# LiPoLoader.net
KiCad netlist of a schematic drawn in EAGLE
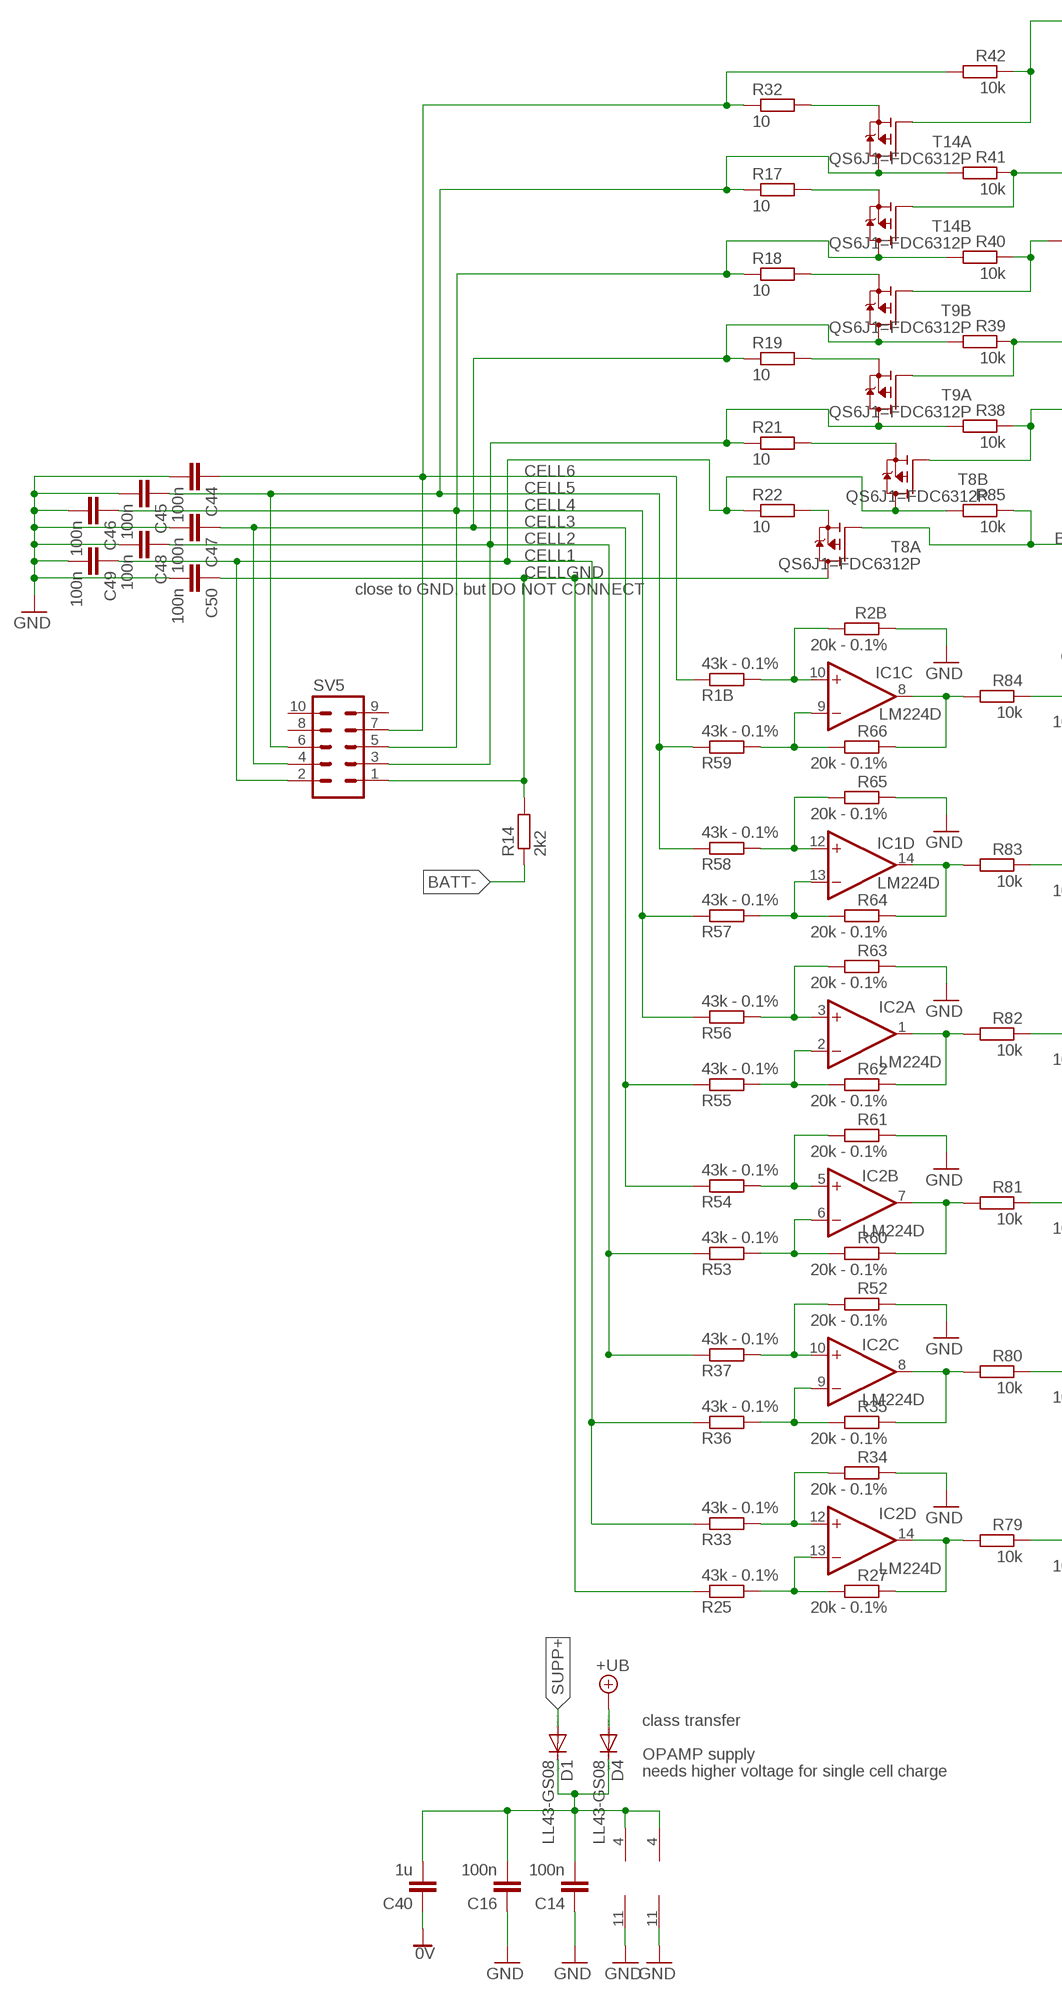
[diagram p0: schematic, sheet 1, part 1 of 2]
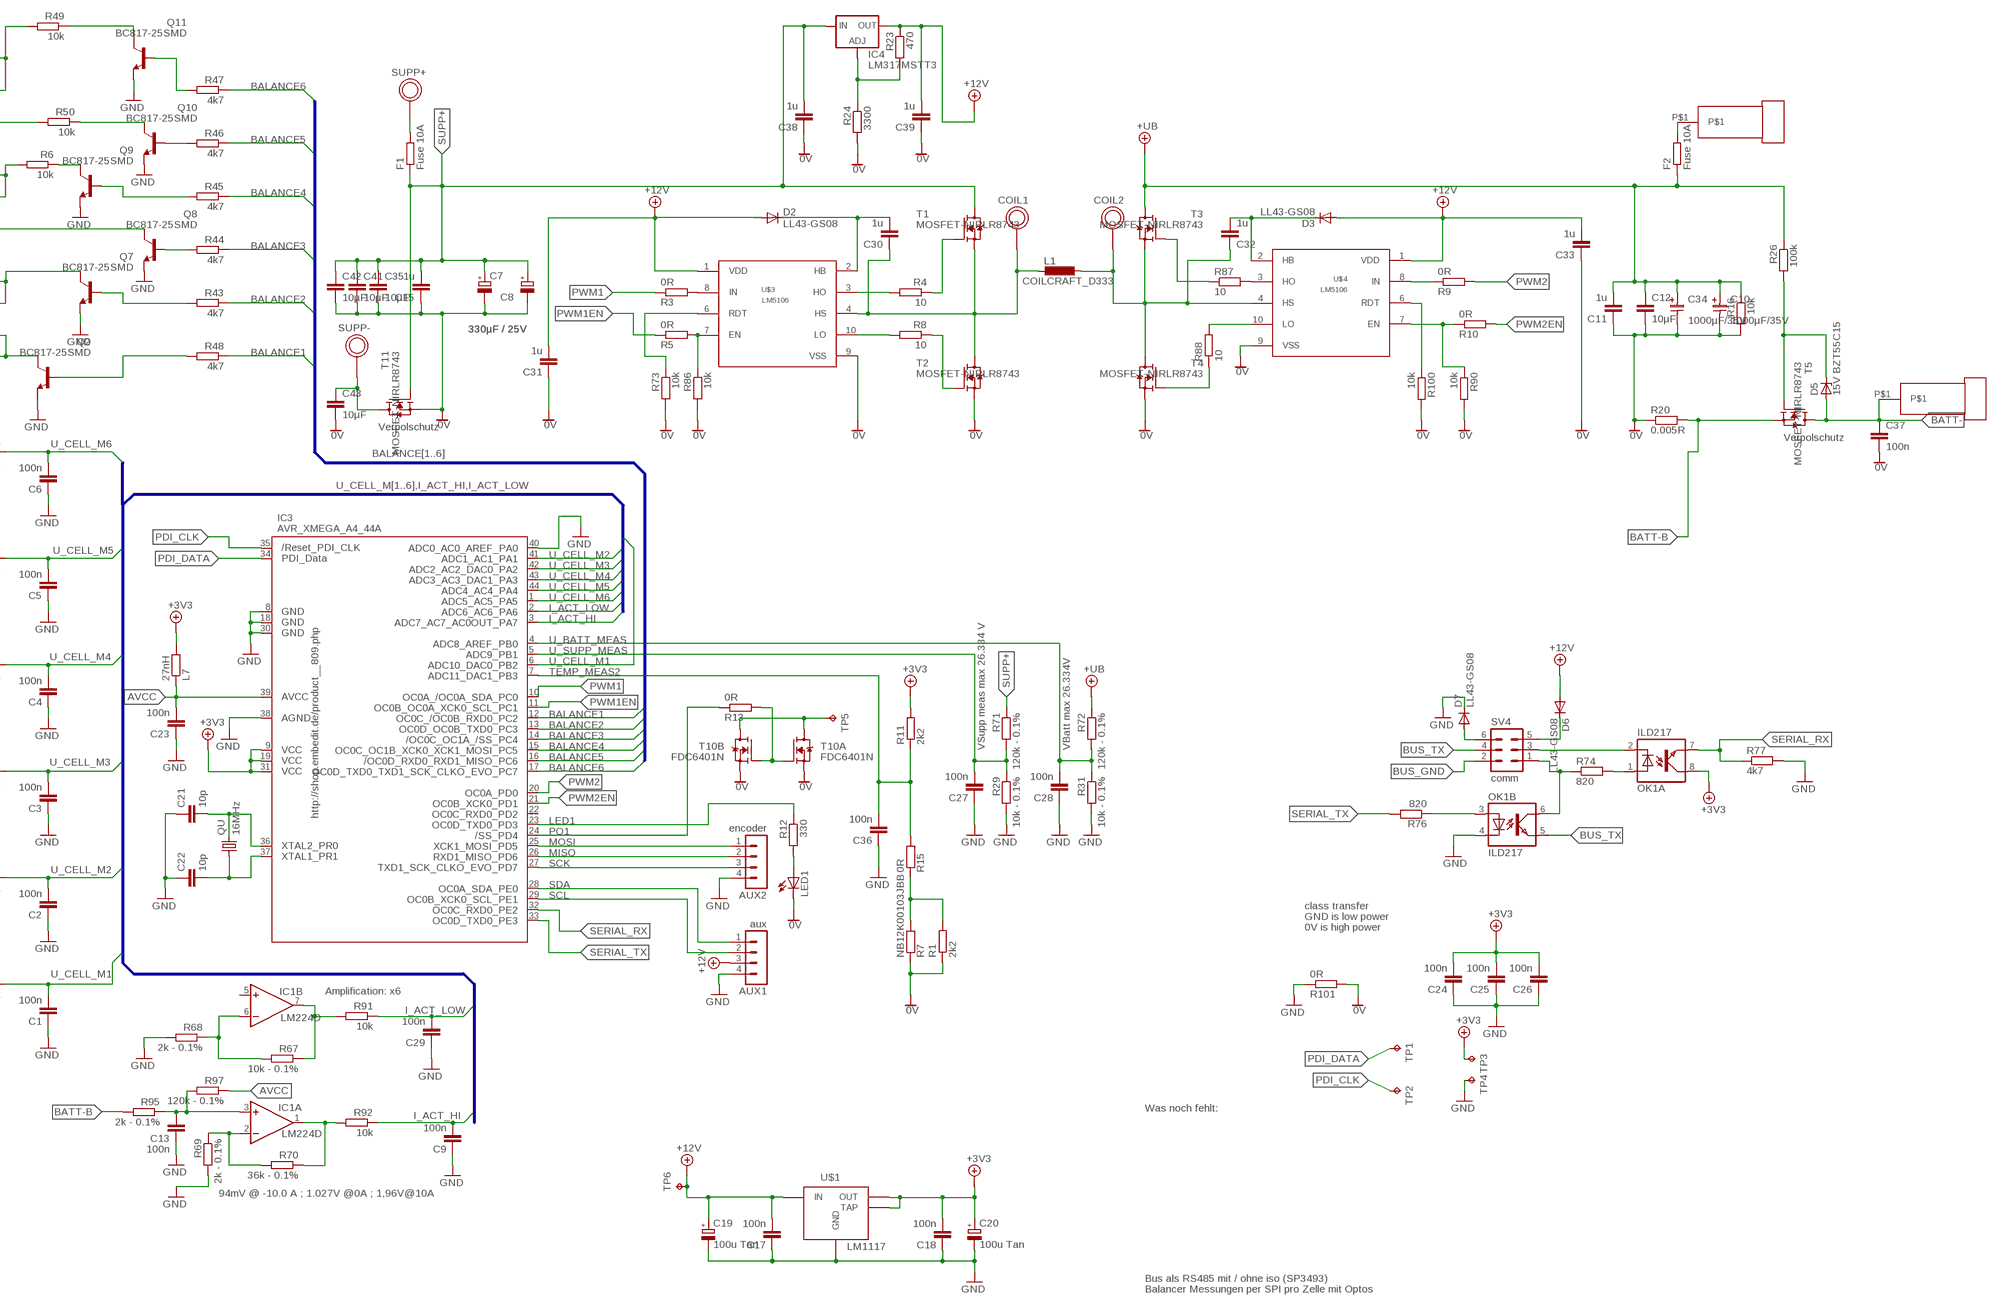
[diagram p1: schematic, sheet 1, part 2 of 2]

(export (version "E")
  (design (tool "Eeschema 10.0.6"))
  (components
    (comp (ref "AUX1")
      (value "aux")
      (footprint "eagle-import:MA04-1")
      (libsource (lib "eagle-import") (part "MA04-1"))
    )
    (comp (ref "AUX2")
      (value "encoder")
      (footprint "eagle-import:MA04-1")
      (libsource (lib "eagle-import") (part "MA04-1"))
    )
    (comp (ref "C1")
      (value "100n")
      (footprint "eagle-import:C0603K")
      (libsource (lib "eagle-import") (part "C-EUC0603K"))
    )
    (comp (ref "C2")
      (value "100n")
      (footprint "eagle-import:C0603K")
      (libsource (lib "eagle-import") (part "C-EUC0603K"))
    )
    (comp (ref "C3")
      (value "100n")
      (footprint "eagle-import:C0603K")
      (libsource (lib "eagle-import") (part "C-EUC0603K"))
    )
    (comp (ref "C4")
      (value "100n")
      (footprint "eagle-import:C0603K")
      (libsource (lib "eagle-import") (part "C-EUC0603K"))
    )
    (comp (ref "C5")
      (value "100n")
      (footprint "eagle-import:C0603K")
      (libsource (lib "eagle-import") (part "C-EUC0603K"))
    )
    (comp (ref "C6")
      (value "100n")
      (footprint "eagle-import:C0603K")
      (libsource (lib "eagle-import") (part "C-EUC0603K"))
    )
    (comp (ref "C7")
      (value "330µF / 25V")
      (footprint "eagle-import:E3,5-8")
      (libsource (lib "eagle-import") (part "CPOL-EUE3.5-8"))
    )
    (comp (ref "C8")
      (value "330µF / 25V")
      (footprint "eagle-import:E3,5-8")
      (libsource (lib "eagle-import") (part "CPOL-EUE3.5-8"))
    )
    (comp (ref "C9")
      (value "100n")
      (footprint "eagle-import:C0603K")
      (libsource (lib "eagle-import") (part "C-EUC0603K"))
    )
    (comp (ref "C10")
      (value "1000µF/35V")
      (footprint "eagle-import:E5-13-L")
      (libsource (lib "eagle-import") (part "CPOL"))
    )
    (comp (ref "C11")
      (value "1u")
      (footprint "eagle-import:C1206K")
      (libsource (lib "eagle-import") (part "C-EUC1206K"))
    )
    (comp (ref "C12")
      (value "10µF")
      (footprint "eagle-import:C1206K")
      (libsource (lib "eagle-import") (part "C-EUC1206K"))
    )
    (comp (ref "C13")
      (value "100n")
      (footprint "eagle-import:C0603K")
      (libsource (lib "eagle-import") (part "C-EUC0603K"))
    )
    (comp (ref "C14")
      (value "100n")
      (footprint "eagle-import:C0603K")
      (libsource (lib "eagle-import") (part "C-EUC0603K"))
    )
    (comp (ref "C15")
      (value "1u")
      (footprint "eagle-import:C1206K")
      (libsource (lib "eagle-import") (part "C-EUC1206K"))
    )
    (comp (ref "C16")
      (value "100n")
      (footprint "eagle-import:C0603K")
      (libsource (lib "eagle-import") (part "C-EUC0603K"))
    )
    (comp (ref "C17")
      (value "100n")
      (footprint "eagle-import:C0603K")
      (libsource (lib "eagle-import") (part "C-EUC0603K"))
    )
    (comp (ref "C18")
      (value "100n")
      (footprint "eagle-import:C0603K")
      (libsource (lib "eagle-import") (part "C-EUC0603K"))
    )
    (comp (ref "C19")
      (value "100u Tan")
      (footprint "eagle-import:SMC_C")
      (libsource (lib "eagle-import") (part "CPOL-EUSMCC"))
    )
    (comp (ref "C20")
      (value "100u Tan")
      (footprint "eagle-import:SMC_C")
      (libsource (lib "eagle-import") (part "CPOL-EUSMCC"))
    )
    (comp (ref "C21")
      (value "10p")
      (footprint "eagle-import:C0603")
      (libsource (lib "eagle-import") (part "C-EUC0603"))
    )
    (comp (ref "C22")
      (value "10p")
      (footprint "eagle-import:C0603")
      (libsource (lib "eagle-import") (part "C-EUC0603"))
    )
    (comp (ref "C23")
      (value "100n")
      (footprint "eagle-import:C0603K")
      (libsource (lib "eagle-import") (part "C-EUC0603K"))
    )
    (comp (ref "C24")
      (value "100n")
      (footprint "eagle-import:C0603K")
      (libsource (lib "eagle-import") (part "C-EUC0603K"))
    )
    (comp (ref "C25")
      (value "100n")
      (footprint "eagle-import:C0603K")
      (libsource (lib "eagle-import") (part "C-EUC0603K"))
    )
    (comp (ref "C26")
      (value "100n")
      (footprint "eagle-import:C0603K")
      (libsource (lib "eagle-import") (part "C-EUC0603K"))
    )
    (comp (ref "C27")
      (value "100n")
      (footprint "eagle-import:C0603K")
      (libsource (lib "eagle-import") (part "C-EUC0603K"))
    )
    (comp (ref "C28")
      (value "100n")
      (footprint "eagle-import:C0603K")
      (libsource (lib "eagle-import") (part "C-EUC0603K"))
    )
    (comp (ref "C29")
      (value "100n")
      (footprint "eagle-import:C0603K")
      (libsource (lib "eagle-import") (part "C-EUC0603K"))
    )
    (comp (ref "C30")
      (value "1u")
      (footprint "eagle-import:C1206K")
      (libsource (lib "eagle-import") (part "C-EUC1206K"))
    )
    (comp (ref "C31")
      (value "1u")
      (footprint "eagle-import:C1206K")
      (libsource (lib "eagle-import") (part "C-EUC1206K"))
    )
    (comp (ref "C32")
      (value "1u")
      (footprint "eagle-import:C1206K")
      (libsource (lib "eagle-import") (part "C-EUC1206K"))
    )
    (comp (ref "C33")
      (value "1u")
      (footprint "eagle-import:C1206K")
      (libsource (lib "eagle-import") (part "C-EUC1206K"))
    )
    (comp (ref "C34")
      (value "1000µF/35V")
      (footprint "eagle-import:E5-13-L")
      (libsource (lib "eagle-import") (part "CPOL"))
    )
    (comp (ref "C35")
      (value "10µF")
      (footprint "eagle-import:C1206K")
      (libsource (lib "eagle-import") (part "C-EUC1206K"))
    )
    (comp (ref "C36")
      (value "100n")
      (footprint "eagle-import:C0603K")
      (libsource (lib "eagle-import") (part "C-EUC0603K"))
    )
    (comp (ref "C37")
      (value "100n")
      (footprint "eagle-import:C0603K")
      (libsource (lib "eagle-import") (part "C-EUC0603K"))
    )
    (comp (ref "C38")
      (value "1u")
      (footprint "eagle-import:C1206K")
      (libsource (lib "eagle-import") (part "C-EUC1206K"))
    )
    (comp (ref "C39")
      (value "1u")
      (footprint "eagle-import:C1206K")
      (libsource (lib "eagle-import") (part "C-EUC1206K"))
    )
    (comp (ref "C40")
      (value "1u")
      (footprint "eagle-import:C1206K")
      (libsource (lib "eagle-import") (part "C-EUC1206K"))
    )
    (comp (ref "C41")
      (value "10µF")
      (footprint "eagle-import:C1206K")
      (libsource (lib "eagle-import") (part "C-EUC1206K"))
    )
    (comp (ref "C42")
      (value "10µF")
      (footprint "eagle-import:C1206K")
      (libsource (lib "eagle-import") (part "C-EUC1206K"))
    )
    (comp (ref "C43")
      (value "10µF")
      (footprint "eagle-import:C1206K")
      (libsource (lib "eagle-import") (part "C-EUC1206K"))
    )
    (comp (ref "C44")
      (value "100n")
      (footprint "eagle-import:C0603K")
      (libsource (lib "eagle-import") (part "C-EUC0603K"))
    )
    (comp (ref "C45")
      (value "100n")
      (footprint "eagle-import:C0603K")
      (libsource (lib "eagle-import") (part "C-EUC0603K"))
    )
    (comp (ref "C46")
      (value "100n")
      (footprint "eagle-import:C0603K")
      (libsource (lib "eagle-import") (part "C-EUC0603K"))
    )
    (comp (ref "C47")
      (value "100n")
      (footprint "eagle-import:C0603K")
      (libsource (lib "eagle-import") (part "C-EUC0603K"))
    )
    (comp (ref "C48")
      (value "100n")
      (footprint "eagle-import:C0603K")
      (libsource (lib "eagle-import") (part "C-EUC0603K"))
    )
    (comp (ref "C49")
      (value "100n")
      (footprint "eagle-import:C0603K")
      (libsource (lib "eagle-import") (part "C-EUC0603K"))
    )
    (comp (ref "C50")
      (value "100n")
      (footprint "eagle-import:C0603K")
      (libsource (lib "eagle-import") (part "C-EUC0603K"))
    )
    (comp (ref "COIL1")
      (value "SOLPAD3MM")
      (footprint "eagle-import:SOLPAD3MM")
      (libsource (lib "eagle-import") (part "SOLPAD3MM"))
    )
    (comp (ref "COIL2")
      (value "SOLPAD3MM")
      (footprint "eagle-import:SOLPAD3MM")
      (libsource (lib "eagle-import") (part "SOLPAD3MM"))
    )
    (comp (ref "D1")
      (value "LL43-GS08")
      (footprint "eagle-import:SOD80C")
      (libsource (lib "eagle-import") (part "DIODE-SOD80C"))
    )
    (comp (ref "D2")
      (value "LL43-GS08")
      (footprint "eagle-import:SOD80C")
      (libsource (lib "eagle-import") (part "DIODE-SOD80C"))
    )
    (comp (ref "D3")
      (value "LL43-GS08")
      (footprint "eagle-import:SOD80C")
      (libsource (lib "eagle-import") (part "DIODE-SOD80C"))
    )
    (comp (ref "D4")
      (value "LL43-GS08")
      (footprint "eagle-import:SOD80C")
      (libsource (lib "eagle-import") (part "DIODE-SOD80C"))
    )
    (comp (ref "D5")
      (value "15V BZT55C15")
      (footprint "eagle-import:SOD80C")
      (libsource (lib "eagle-import") (part "ZENER-DIODESOD80C"))
    )
    (comp (ref "D6")
      (value "LL43-GS08")
      (footprint "eagle-import:SOD80C")
      (libsource (lib "eagle-import") (part "DIODE-SOD80C"))
    )
    (comp (ref "D7")
      (value "LL43-GS08")
      (footprint "eagle-import:SOD80C")
      (libsource (lib "eagle-import") (part "DIODE-SOD80C"))
    )
    (comp (ref "F1")
      (value "Fuse 10A")
      (footprint "eagle-import:WSC2515")
      (libsource (lib "eagle-import") (part "R-EU_WSC2515"))
    )
    (comp (ref "F2")
      (value "Fuse 10A")
      (footprint "eagle-import:WSC2515")
      (libsource (lib "eagle-import") (part "R-EU_WSC2515"))
    )
    (comp (ref "IC1")
      (value "LM224D")
      (footprint "eagle-import:SO14")
      (fields (field (name "BEST") "Farnell 1426352"))
      (libsource (lib "eagle-import") (part "LM324D"))
    )
    (comp (ref "IC2")
      (value "LM224D")
      (footprint "eagle-import:SO14")
      (fields (field (name "BEST") "Farnell 1426352"))
      (libsource (lib "eagle-import") (part "LM324D"))
    )
    (comp (ref "IC3")
      (value "AVR_XMEGA_A4_44A")
      (footprint "eagle-import:TQFP44")
      (fields (field (name "BEST") "http://shop.embedit.de/product__809.php"))
      (libsource (lib "eagle-import") (part "AVR_XMEGA_A4_44A"))
    )
    (comp (ref "IC4")
      (value "LM317MSTT3")
      (footprint "eagle-import:SOT223")
      (libsource (lib "eagle-import") (part "LM317?MSTT3"))
    )
    (comp (ref "L1")
      (value "COILCRAFT_D333")
      (footprint "eagle-import:D333")
      (libsource (lib "eagle-import") (part "COILCRAFT_D333"))
    )
    (comp (ref "L7")
      (value "27nH")
      (footprint "eagle-import:R0603")
      (libsource (lib "eagle-import") (part "R-EU_R0603"))
    )
    (comp (ref "LED1")
      (value "LED5MM")
      (footprint "eagle-import:LED5MM")
      (libsource (lib "eagle-import") (part "LED5MM"))
    )
    (comp (ref "OK1")
      (value "ILD217")
      (footprint "eagle-import:SOIC08")
      (fields
        (field (name "MF") "VISHAY/TELEFUNKEN")
        (field (name "MPN") "ILD217T")
        (field (name "BEST") "Farnell 1469512")
      )
      (libsource (lib "eagle-import") (part "ILD217"))
    )
    (comp (ref "Q2")
      (value "BC817-25SMD")
      (footprint "eagle-import:SOT23-BEC")
      (libsource (lib "eagle-import") (part "BC817SMD-25"))
    )
    (comp (ref "Q7")
      (value "BC817-25SMD")
      (footprint "eagle-import:SOT23-BEC")
      (libsource (lib "eagle-import") (part "BC817SMD-25"))
    )
    (comp (ref "Q8")
      (value "BC817-25SMD")
      (footprint "eagle-import:SOT23-BEC")
      (libsource (lib "eagle-import") (part "BC817SMD-25"))
    )
    (comp (ref "Q9")
      (value "BC817-25SMD")
      (footprint "eagle-import:SOT23-BEC")
      (libsource (lib "eagle-import") (part "BC817SMD-25"))
    )
    (comp (ref "Q10")
      (value "BC817-25SMD")
      (footprint "eagle-import:SOT23-BEC")
      (libsource (lib "eagle-import") (part "BC817SMD-25"))
    )
    (comp (ref "Q11")
      (value "BC817-25SMD")
      (footprint "eagle-import:SOT23-BEC")
      (libsource (lib "eagle-import") (part "BC817SMD-25"))
    )
    (comp (ref "QU")
      (value "16MHz")
      (footprint "eagle-import:HC49U-V")
      (libsource (lib "eagle-import") (part "CRYSTALHC49U-V"))
    )
    (comp (ref "R1")
      (value "2k2")
      (footprint "eagle-import:R0603")
      (libsource (lib "eagle-import") (part "R-EU_R0603"))
    )
    (comp (ref "R1B")
      (value "43k - 0.1%")
      (footprint "eagle-import:R0603")
      (libsource (lib "eagle-import") (part "R-EU_R0603"))
    )
    (comp (ref "R2B")
      (value "20k - 0.1%")
      (footprint "eagle-import:R0603")
      (libsource (lib "eagle-import") (part "R-EU_R0603"))
    )
    (comp (ref "R3")
      (value "0R")
      (footprint "eagle-import:R0603")
      (libsource (lib "eagle-import") (part "R-EU_R0603"))
    )
    (comp (ref "R4")
      (value "10")
      (footprint "eagle-import:R0603")
      (libsource (lib "eagle-import") (part "R-EU_R0603"))
    )
    (comp (ref "R5")
      (value "0R")
      (footprint "eagle-import:R0603")
      (libsource (lib "eagle-import") (part "R-EU_R0603"))
    )
    (comp (ref "R6")
      (value "10k")
      (footprint "eagle-import:R0603")
      (libsource (lib "eagle-import") (part "R-EU_R0603"))
    )
    (comp (ref "R7")
      (value "NB12K00103JBB")
      (footprint "eagle-import:R0603")
      (libsource (lib "eagle-import") (part "R-EU_R0603"))
    )
    (comp (ref "R8")
      (value "10")
      (footprint "eagle-import:R0603")
      (libsource (lib "eagle-import") (part "R-EU_R0603"))
    )
    (comp (ref "R9")
      (value "0R")
      (footprint "eagle-import:R0603")
      (libsource (lib "eagle-import") (part "R-EU_R0603"))
    )
    (comp (ref "R10")
      (value "0R")
      (footprint "eagle-import:R0603")
      (libsource (lib "eagle-import") (part "R-EU_R0603"))
    )
    (comp (ref "R11")
      (value "2k2")
      (footprint "eagle-import:R0603")
      (libsource (lib "eagle-import") (part "R-EU_R0603"))
    )
    (comp (ref "R12")
      (value "330")
      (footprint "eagle-import:R0805")
      (libsource (lib "eagle-import") (part "R-EU_R0805"))
    )
    (comp (ref "R13")
      (value "0R")
      (footprint "eagle-import:R0603")
      (libsource (lib "eagle-import") (part "R-EU_R0603"))
    )
    (comp (ref "R14")
      (value "2k2")
      (footprint "eagle-import:R0603")
      (libsource (lib "eagle-import") (part "R-EU_R0603"))
    )
    (comp (ref "R15")
      (value "0R")
      (footprint "eagle-import:R0603")
      (libsource (lib "eagle-import") (part "R-EU_R0603"))
    )
    (comp (ref "R16")
      (value "10k")
      (footprint "eagle-import:R0603")
      (libsource (lib "eagle-import") (part "R-EU_R0603"))
    )
    (comp (ref "R17")
      (value "10")
      (footprint "eagle-import:R2512")
      (libsource (lib "eagle-import") (part "R-EU_R2512"))
    )
    (comp (ref "R18")
      (value "10")
      (footprint "eagle-import:R2512")
      (libsource (lib "eagle-import") (part "R-EU_R2512"))
    )
    (comp (ref "R19")
      (value "10")
      (footprint "eagle-import:R2512")
      (libsource (lib "eagle-import") (part "R-EU_R2512"))
    )
    (comp (ref "R20")
      (value "0.005R")
      (footprint "eagle-import:R2010")
      (libsource (lib "eagle-import") (part "R-EU_R2010"))
    )
    (comp (ref "R21")
      (value "10")
      (footprint "eagle-import:R2512")
      (libsource (lib "eagle-import") (part "R-EU_R2512"))
    )
    (comp (ref "R22")
      (value "10")
      (footprint "eagle-import:R2512")
      (libsource (lib "eagle-import") (part "R-EU_R2512"))
    )
    (comp (ref "R23")
      (value "470")
      (footprint "eagle-import:R0603")
      (libsource (lib "eagle-import") (part "R-EU_R0603"))
    )
    (comp (ref "R24")
      (value "3300")
      (footprint "eagle-import:R0603")
      (libsource (lib "eagle-import") (part "R-EU_R0603"))
    )
    (comp (ref "R25")
      (value "43k - 0.1%")
      (footprint "eagle-import:R0603")
      (libsource (lib "eagle-import") (part "R-EU_R0603"))
    )
    (comp (ref "R26")
      (value "100k")
      (footprint "eagle-import:R0603")
      (libsource (lib "eagle-import") (part "R-EU_R0603"))
    )
    (comp (ref "R27")
      (value "20k - 0.1%")
      (footprint "eagle-import:R0603")
      (libsource (lib "eagle-import") (part "R-EU_R0603"))
    )
    (comp (ref "R29")
      (value "10k - 0.1%")
      (footprint "eagle-import:R0603")
      (libsource (lib "eagle-import") (part "R-EU_R0603"))
    )
    (comp (ref "R31")
      (value "10k - 0.1%")
      (footprint "eagle-import:R0603")
      (libsource (lib "eagle-import") (part "R-EU_R0603"))
    )
    (comp (ref "R32")
      (value "10")
      (footprint "eagle-import:R2512")
      (libsource (lib "eagle-import") (part "R-EU_R2512"))
    )
    (comp (ref "R33")
      (value "43k - 0.1%")
      (footprint "eagle-import:R0603")
      (libsource (lib "eagle-import") (part "R-EU_R0603"))
    )
    (comp (ref "R34")
      (value "20k - 0.1%")
      (footprint "eagle-import:R0603")
      (libsource (lib "eagle-import") (part "R-EU_R0603"))
    )
    (comp (ref "R35")
      (value "20k - 0.1%")
      (footprint "eagle-import:R0603")
      (libsource (lib "eagle-import") (part "R-EU_R0603"))
    )
    (comp (ref "R36")
      (value "43k - 0.1%")
      (footprint "eagle-import:R0603")
      (libsource (lib "eagle-import") (part "R-EU_R0603"))
    )
    (comp (ref "R37")
      (value "43k - 0.1%")
      (footprint "eagle-import:R0603")
      (libsource (lib "eagle-import") (part "R-EU_R0603"))
    )
    (comp (ref "R38")
      (value "10k")
      (footprint "eagle-import:R0603")
      (libsource (lib "eagle-import") (part "R-EU_R0603"))
    )
    (comp (ref "R39")
      (value "10k")
      (footprint "eagle-import:R0603")
      (libsource (lib "eagle-import") (part "R-EU_R0603"))
    )
    (comp (ref "R40")
      (value "10k")
      (footprint "eagle-import:R0603")
      (libsource (lib "eagle-import") (part "R-EU_R0603"))
    )
    (comp (ref "R41")
      (value "10k")
      (footprint "eagle-import:R0603")
      (libsource (lib "eagle-import") (part "R-EU_R0603"))
    )
    (comp (ref "R42")
      (value "10k")
      (footprint "eagle-import:R0603")
      (libsource (lib "eagle-import") (part "R-EU_R0603"))
    )
    (comp (ref "R43")
      (value "4k7")
      (footprint "eagle-import:R0603")
      (libsource (lib "eagle-import") (part "R-EU_R0603"))
    )
    (comp (ref "R44")
      (value "4k7")
      (footprint "eagle-import:R0603")
      (libsource (lib "eagle-import") (part "R-EU_R0603"))
    )
    (comp (ref "R45")
      (value "4k7")
      (footprint "eagle-import:R0603")
      (libsource (lib "eagle-import") (part "R-EU_R0603"))
    )
    (comp (ref "R46")
      (value "4k7")
      (footprint "eagle-import:R0603")
      (libsource (lib "eagle-import") (part "R-EU_R0603"))
    )
    (comp (ref "R47")
      (value "4k7")
      (footprint "eagle-import:R0603")
      (libsource (lib "eagle-import") (part "R-EU_R0603"))
    )
    (comp (ref "R48")
      (value "4k7")
      (footprint "eagle-import:R0603")
      (libsource (lib "eagle-import") (part "R-EU_R0603"))
    )
    (comp (ref "R49")
      (value "10k")
      (footprint "eagle-import:R0603")
      (libsource (lib "eagle-import") (part "R-EU_R0603"))
    )
    (comp (ref "R50")
      (value "10k")
      (footprint "eagle-import:R0603")
      (libsource (lib "eagle-import") (part "R-EU_R0603"))
    )
    (comp (ref "R52")
      (value "20k - 0.1%")
      (footprint "eagle-import:R0603")
      (libsource (lib "eagle-import") (part "R-EU_R0603"))
    )
    (comp (ref "R53")
      (value "43k - 0.1%")
      (footprint "eagle-import:R0603")
      (libsource (lib "eagle-import") (part "R-EU_R0603"))
    )
    (comp (ref "R54")
      (value "43k - 0.1%")
      (footprint "eagle-import:R0603")
      (libsource (lib "eagle-import") (part "R-EU_R0603"))
    )
    (comp (ref "R55")
      (value "43k - 0.1%")
      (footprint "eagle-import:R0603")
      (libsource (lib "eagle-import") (part "R-EU_R0603"))
    )
    (comp (ref "R56")
      (value "43k - 0.1%")
      (footprint "eagle-import:R0603")
      (libsource (lib "eagle-import") (part "R-EU_R0603"))
    )
    (comp (ref "R57")
      (value "43k - 0.1%")
      (footprint "eagle-import:R0603")
      (libsource (lib "eagle-import") (part "R-EU_R0603"))
    )
    (comp (ref "R58")
      (value "43k - 0.1%")
      (footprint "eagle-import:R0603")
      (libsource (lib "eagle-import") (part "R-EU_R0603"))
    )
    (comp (ref "R59")
      (value "43k - 0.1%")
      (footprint "eagle-import:R0603")
      (libsource (lib "eagle-import") (part "R-EU_R0603"))
    )
    (comp (ref "R60")
      (value "20k - 0.1%")
      (footprint "eagle-import:R0603")
      (libsource (lib "eagle-import") (part "R-EU_R0603"))
    )
    (comp (ref "R61")
      (value "20k - 0.1%")
      (footprint "eagle-import:R0603")
      (libsource (lib "eagle-import") (part "R-EU_R0603"))
    )
    (comp (ref "R62")
      (value "20k - 0.1%")
      (footprint "eagle-import:R0603")
      (libsource (lib "eagle-import") (part "R-EU_R0603"))
    )
    (comp (ref "R63")
      (value "20k - 0.1%")
      (footprint "eagle-import:R0603")
      (libsource (lib "eagle-import") (part "R-EU_R0603"))
    )
    (comp (ref "R64")
      (value "20k - 0.1%")
      (footprint "eagle-import:R0603")
      (libsource (lib "eagle-import") (part "R-EU_R0603"))
    )
    (comp (ref "R65")
      (value "20k - 0.1%")
      (footprint "eagle-import:R0603")
      (libsource (lib "eagle-import") (part "R-EU_R0603"))
    )
    (comp (ref "R66")
      (value "20k - 0.1%")
      (footprint "eagle-import:R0603")
      (libsource (lib "eagle-import") (part "R-EU_R0603"))
    )
    (comp (ref "R67")
      (value "10k - 0.1%")
      (footprint "eagle-import:R0603")
      (libsource (lib "eagle-import") (part "R-EU_R0603"))
    )
    (comp (ref "R68")
      (value "2k - 0.1%")
      (footprint "eagle-import:R0603")
      (libsource (lib "eagle-import") (part "R-EU_R0603"))
    )
    (comp (ref "R69")
      (value "2k - 0.1%")
      (footprint "eagle-import:R0603")
      (libsource (lib "eagle-import") (part "R-EU_R0603"))
    )
    (comp (ref "R70")
      (value "36k - 0.1%")
      (footprint "eagle-import:R0603")
      (libsource (lib "eagle-import") (part "R-EU_R0603"))
    )
    (comp (ref "R71")
      (value "120k - 0.1%")
      (footprint "eagle-import:R0603")
      (libsource (lib "eagle-import") (part "R-EU_R0603"))
    )
    (comp (ref "R72")
      (value "120k - 0.1%")
      (footprint "eagle-import:R0603")
      (libsource (lib "eagle-import") (part "R-EU_R0603"))
    )
    (comp (ref "R73")
      (value "10k")
      (footprint "eagle-import:R0603")
      (libsource (lib "eagle-import") (part "R-EU_R0603"))
    )
    (comp (ref "R74")
      (value "820")
      (footprint "eagle-import:R0603")
      (libsource (lib "eagle-import") (part "R-EU_R0603"))
    )
    (comp (ref "R76")
      (value "820")
      (footprint "eagle-import:R0603")
      (libsource (lib "eagle-import") (part "R-EU_R0603"))
    )
    (comp (ref "R77")
      (value "4k7")
      (footprint "eagle-import:R0603")
      (libsource (lib "eagle-import") (part "R-EU_R0603"))
    )
    (comp (ref "R79")
      (value "10k")
      (footprint "eagle-import:R0603")
      (libsource (lib "eagle-import") (part "R-EU_R0603"))
    )
    (comp (ref "R80")
      (value "10k")
      (footprint "eagle-import:R0603")
      (libsource (lib "eagle-import") (part "R-EU_R0603"))
    )
    (comp (ref "R81")
      (value "10k")
      (footprint "eagle-import:R0603")
      (libsource (lib "eagle-import") (part "R-EU_R0603"))
    )
    (comp (ref "R82")
      (value "10k")
      (footprint "eagle-import:R0603")
      (libsource (lib "eagle-import") (part "R-EU_R0603"))
    )
    (comp (ref "R83")
      (value "10k")
      (footprint "eagle-import:R0603")
      (libsource (lib "eagle-import") (part "R-EU_R0603"))
    )
    (comp (ref "R84")
      (value "10k")
      (footprint "eagle-import:R0603")
      (libsource (lib "eagle-import") (part "R-EU_R0603"))
    )
    (comp (ref "R85")
      (value "10k")
      (footprint "eagle-import:R0603")
      (libsource (lib "eagle-import") (part "R-EU_R0603"))
    )
    (comp (ref "R86")
      (value "10k")
      (footprint "eagle-import:R0603")
      (libsource (lib "eagle-import") (part "R-EU_R0603"))
    )
    (comp (ref "R87")
      (value "10")
      (footprint "eagle-import:R0603")
      (libsource (lib "eagle-import") (part "R-EU_R0603"))
    )
    (comp (ref "R88")
      (value "10")
      (footprint "eagle-import:R0603")
      (libsource (lib "eagle-import") (part "R-EU_R0603"))
    )
    (comp (ref "R90")
      (value "10k")
      (footprint "eagle-import:R0603")
      (libsource (lib "eagle-import") (part "R-EU_R0603"))
    )
    (comp (ref "R91")
      (value "10k")
      (footprint "eagle-import:R0603")
      (libsource (lib "eagle-import") (part "R-EU_R0603"))
    )
    (comp (ref "R92")
      (value "10k")
      (footprint "eagle-import:R0603")
      (libsource (lib "eagle-import") (part "R-EU_R0603"))
    )
    (comp (ref "R95")
      (value "2k - 0.1%")
      (footprint "eagle-import:R0603")
      (libsource (lib "eagle-import") (part "R-EU_R0603"))
    )
    (comp (ref "R97")
      (value "120k - 0.1%")
      (footprint "eagle-import:R0603")
      (libsource (lib "eagle-import") (part "R-EU_R0603"))
    )
    (comp (ref "R100")
      (value "10k")
      (footprint "eagle-import:R0603")
      (libsource (lib "eagle-import") (part "R-EU_R0603"))
    )
    (comp (ref "R101")
      (value "0R")
      (footprint "eagle-import:R0603")
      (libsource (lib "eagle-import") (part "R-EU_R0603"))
    )
    (comp (ref "SUPP+")
      (value "SOLPAD3MM")
      (footprint "eagle-import:SOLPAD3MM")
      (libsource (lib "eagle-import") (part "SOLPAD3MM"))
    )
    (comp (ref "SUPP-")
      (value "SOLPAD3MM")
      (footprint "eagle-import:SOLPAD3MM")
      (libsource (lib "eagle-import") (part "SOLPAD3MM"))
    )
    (comp (ref "SV4")
      (value "comm")
      (footprint "eagle-import:ML6L")
      (libsource (lib "eagle-import") (part "ML6L"))
    )
    (comp (ref "SV5")
      (value "CON_BOX_10L")
      (footprint "eagle-import:ML10L")
      (libsource (lib "eagle-import") (part "CON_BOX_10L"))
    )
    (comp (ref "T1")
      (value "MOSFET-NIRLR8743")
      (footprint "eagle-import:DPAK")
      (libsource (lib "eagle-import") (part "MOSFET-NIRLR8743"))
    )
    (comp (ref "T2")
      (value "MOSFET-NIRLR8743")
      (footprint "eagle-import:DPAK")
      (libsource (lib "eagle-import") (part "MOSFET-NIRLR8743"))
    )
    (comp (ref "T3")
      (value "MOSFET-NIRLR8743")
      (footprint "eagle-import:DPAK")
      (libsource (lib "eagle-import") (part "MOSFET-NIRLR8743"))
    )
    (comp (ref "T4")
      (value "MOSFET-NIRLR8743")
      (footprint "eagle-import:DPAK")
      (libsource (lib "eagle-import") (part "MOSFET-NIRLR8743"))
    )
    (comp (ref "T5")
      (value "MOSFET-NIRLR8743")
      (footprint "eagle-import:DPAK")
      (libsource (lib "eagle-import") (part "MOSFET-NIRLR8743"))
    )
    (comp (ref "T8")
      (value "QS6J1=FDC6312P")
      (footprint "eagle-import:SUPERSOT-6")
      (libsource (lib "eagle-import") (part "QS6J1=FDC6312P"))
    )
    (comp (ref "T9")
      (value "QS6J1=FDC6312P")
      (footprint "eagle-import:SUPERSOT-6")
      (libsource (lib "eagle-import") (part "QS6J1=FDC6312P"))
    )
    (comp (ref "T10")
      (value "FDC6401N")
      (footprint "eagle-import:SUPERSOT-6")
      (libsource (lib "eagle-import") (part "FDC6401N"))
    )
    (comp (ref "T11")
      (value "MOSFET-NIRLR8743")
      (footprint "eagle-import:DPAK")
      (libsource (lib "eagle-import") (part "MOSFET-NIRLR8743"))
    )
    (comp (ref "T14")
      (value "QS6J1=FDC6312P")
      (footprint "eagle-import:SUPERSOT-6")
      (libsource (lib "eagle-import") (part "QS6J1=FDC6312P"))
    )
    (comp (ref "TP1")
      (value "TPTP15R")
      (footprint "eagle-import:TP15R")
      (libsource (lib "eagle-import") (part "TPTP15R"))
    )
    (comp (ref "TP2")
      (value "TPTP15R")
      (footprint "eagle-import:TP15R")
      (libsource (lib "eagle-import") (part "TPTP15R"))
    )
    (comp (ref "TP3")
      (value "TPTP15R")
      (footprint "eagle-import:TP15R")
      (libsource (lib "eagle-import") (part "TPTP15R"))
    )
    (comp (ref "TP4")
      (value "TPTP15R")
      (footprint "eagle-import:TP15R")
      (libsource (lib "eagle-import") (part "TPTP15R"))
    )
    (comp (ref "TP5")
      (value "TPTP15R")
      (footprint "eagle-import:TP15R")
      (libsource (lib "eagle-import") (part "TPTP15R"))
    )
    (comp (ref "TP6")
      (value "TPTP15R")
      (footprint "eagle-import:TP15R")
      (libsource (lib "eagle-import") (part "TPTP15R"))
    )
    (comp (ref "U$1")
      (value "LM1117")
      (footprint "eagle-import:SOT223")
      (libsource (lib "eagle-import") (part "LM1117"))
    )
    (comp (ref "U$3")
      (value "LM5106")
      (footprint "eagle-import:MSOP10W")
      (libsource (lib "eagle-import") (part "LM5106"))
    )
    (comp (ref "U$4")
      (value "LM5106")
      (footprint "eagle-import:MSOP10W")
      (libsource (lib "eagle-import") (part "LM5106"))
    )
    (comp (ref "U$5")
      (value "BUCHSE4MM")
      (footprint "eagle-import:BUCHSE4MML")
      (libsource (lib "eagle-import") (part "BUCHSE4MM"))
    )
    (comp (ref "U$6")
      (value "BUCHSE4MM")
      (footprint "eagle-import:BUCHSE4MML")
      (libsource (lib "eagle-import") (part "BUCHSE4MM"))
    )
  )
  (nets
    (net (code "1") (name "+3V3") (class "Default")
      (node (ref "C18") (pin "2") (pinfunction "2_2") (pintype "passive"))
      (node (ref "C20") (pin "+") (pinfunction "+_+") (pintype "passive"))
      (node (ref "C24") (pin "2") (pinfunction "2_2") (pintype "passive"))
      (node (ref "C25") (pin "2") (pinfunction "2_2") (pintype "passive"))
      (node (ref "C26") (pin "2") (pinfunction "2_2") (pintype "passive"))
      (node (ref "IC3") (pin "19") (pinfunction "VCC2_19") (pintype "bidirectional"))
      (node (ref "IC3") (pin "31") (pinfunction "VCC3_31") (pintype "bidirectional"))
      (node (ref "IC3") (pin "9") (pinfunction "VCC1_9") (pintype "bidirectional"))
      (node (ref "L7") (pin "2") (pinfunction "2_2") (pintype "passive"))
      (node (ref "OK1") (pin "8") (pinfunction "COL_8") (pintype "passive"))
      (node (ref "R11") (pin "2") (pinfunction "2_2") (pintype "passive"))
      (node (ref "TP3") (pin "TP") (pinfunction "TP_TP") (pintype "input"))
      (node (ref "U$1") (pin "MID") (pinfunction "OUT_MID") (pintype "bidirectional"))
      (node (ref "U$1") (pin "TAP") (pinfunction "TAP_TAP") (pintype "bidirectional"))
    )
    (net (code "2") (name "+12V") (class "Default")
      (node (ref "AUX1") (pin "3") (pinfunction "3_3") (pintype "passive"))
      (node (ref "C17") (pin "2") (pinfunction "2_2") (pintype "passive"))
      (node (ref "C19") (pin "+") (pinfunction "+_+") (pintype "passive"))
      (node (ref "C31") (pin "2") (pinfunction "2_2") (pintype "passive"))
      (node (ref "C33") (pin "2") (pinfunction "2_2") (pintype "passive"))
      (node (ref "C39") (pin "2") (pinfunction "2_2") (pintype "passive"))
      (node (ref "D2") (pin "A") (pinfunction "A_A") (pintype "passive"))
      (node (ref "D3") (pin "A") (pinfunction "A_A") (pintype "passive"))
      (node (ref "D6") (pin "A") (pinfunction "A_A") (pintype "passive"))
      (node (ref "IC4") (pin "4") (pinfunction "OUT_4") (pintype "passive"))
      (node (ref "R23") (pin "1") (pinfunction "1_1") (pintype "passive"))
      (node (ref "TP6") (pin "TP") (pinfunction "TP_TP") (pintype "input"))
      (node (ref "U$1") (pin "RIGHT") (pinfunction "IN_RIGHT") (pintype "bidirectional"))
      (node (ref "U$3") (pin "1") (pinfunction "VDD_1") (pintype "bidirectional"))
      (node (ref "U$4") (pin "1") (pinfunction "VDD_1") (pintype "bidirectional"))
    )
    (net (code "3") (name "+UB") (class "Default")
      (node (ref "C10") (pin "+") (pinfunction "P+_+") (pintype "bidirectional"))
      (node (ref "C11") (pin "2") (pinfunction "2_2") (pintype "passive"))
      (node (ref "C12") (pin "1") (pinfunction "1_1") (pintype "passive"))
      (node (ref "C34") (pin "+") (pinfunction "P+_+") (pintype "bidirectional"))
      (node (ref "D4") (pin "A") (pinfunction "A_A") (pintype "passive"))
      (node (ref "F2") (pin "1") (pinfunction "1_1") (pintype "passive"))
      (node (ref "R16") (pin "1") (pinfunction "1_1") (pintype "passive"))
      (node (ref "R26") (pin "1") (pinfunction "1_1") (pintype "passive"))
      (node (ref "R72") (pin "1") (pinfunction "1_1") (pintype "passive"))
      (node (ref "T3") (pin "4") (pinfunction "D_4") (pintype "passive"))
    )
    (net (code "4") (name "/BALANCE1") (class "Default")
      (node (ref "IC3") (pin "12") (pinfunction "PC2_12") (pintype "bidirectional"))
      (node (ref "R48") (pin "1") (pinfunction "1_1") (pintype "passive"))
    )
    (net (code "5") (name "/BALANCE2") (class "Default")
      (node (ref "IC3") (pin "13") (pinfunction "PC3_13") (pintype "bidirectional"))
      (node (ref "R43") (pin "1") (pinfunction "1_1") (pintype "passive"))
    )
    (net (code "6") (name "/BALANCE3") (class "Default")
      (node (ref "IC3") (pin "14") (pinfunction "PC4_14") (pintype "bidirectional"))
      (node (ref "R44") (pin "1") (pinfunction "1_1") (pintype "passive"))
    )
    (net (code "7") (name "/BALANCE4") (class "Default")
      (node (ref "IC3") (pin "15") (pinfunction "PC5_15") (pintype "bidirectional"))
      (node (ref "R45") (pin "1") (pinfunction "1_1") (pintype "passive"))
    )
    (net (code "8") (name "/BALANCE5") (class "Default")
      (node (ref "IC3") (pin "16") (pinfunction "PC6_16") (pintype "bidirectional"))
      (node (ref "R46") (pin "1") (pinfunction "1_1") (pintype "passive"))
    )
    (net (code "9") (name "/BALANCE6") (class "Default")
      (node (ref "IC3") (pin "17") (pinfunction "PC7_17") (pintype "bidirectional"))
      (node (ref "R47") (pin "1") (pinfunction "1_1") (pintype "passive"))
    )
    (net (code "11") (name "/CELL1") (class "Default")
      (node (ref "C49") (pin "1") (pinfunction "1_1") (pintype "passive"))
      (node (ref "R22") (pin "1") (pinfunction "1_1") (pintype "passive"))
      (node (ref "R33") (pin "1") (pinfunction "1_1") (pintype "passive"))
      (node (ref "R36") (pin "1") (pinfunction "1_1") (pintype "passive"))
      (node (ref "R85") (pin "2") (pinfunction "2_2") (pintype "passive"))
      (node (ref "SV5") (pin "2") (pinfunction "2_2") (pintype "passive"))
      (node (ref "T8") (pin "P$4") (pinfunction "D_P$4") (pintype "passive"))
    )
    (net (code "12") (name "/CELL2") (class "Default")
      (node (ref "C48") (pin "1") (pinfunction "1_1") (pintype "passive"))
      (node (ref "R21") (pin "1") (pinfunction "1_1") (pintype "passive"))
      (node (ref "R37") (pin "1") (pinfunction "1_1") (pintype "passive"))
      (node (ref "R38") (pin "2") (pinfunction "2_2") (pintype "passive"))
      (node (ref "R53") (pin "1") (pinfunction "1_1") (pintype "passive"))
      (node (ref "SV5") (pin "3") (pinfunction "3_3") (pintype "passive"))
      (node (ref "T9") (pin "P$6") (pinfunction "D_P$6") (pintype "passive"))
    )
    (net (code "13") (name "/CELL3") (class "Default")
      (node (ref "C47") (pin "1") (pinfunction "1_1") (pintype "passive"))
      (node (ref "R19") (pin "1") (pinfunction "1_1") (pintype "passive"))
      (node (ref "R39") (pin "2") (pinfunction "2_2") (pintype "passive"))
      (node (ref "R54") (pin "1") (pinfunction "1_1") (pintype "passive"))
      (node (ref "R55") (pin "1") (pinfunction "1_1") (pintype "passive"))
      (node (ref "SV5") (pin "4") (pinfunction "4_4") (pintype "passive"))
      (node (ref "T9") (pin "P$4") (pinfunction "D_P$4") (pintype "passive"))
    )
    (net (code "14") (name "/CELL4") (class "Default")
      (node (ref "C46") (pin "1") (pinfunction "1_1") (pintype "passive"))
      (node (ref "R18") (pin "1") (pinfunction "1_1") (pintype "passive"))
      (node (ref "R40") (pin "2") (pinfunction "2_2") (pintype "passive"))
      (node (ref "R56") (pin "1") (pinfunction "1_1") (pintype "passive"))
      (node (ref "R57") (pin "1") (pinfunction "1_1") (pintype "passive"))
      (node (ref "SV5") (pin "5") (pinfunction "5_5") (pintype "passive"))
      (node (ref "T14") (pin "P$4") (pinfunction "D_P$4") (pintype "passive"))
    )
    (net (code "15") (name "/CELL5") (class "Default")
      (node (ref "C45") (pin "1") (pinfunction "1_1") (pintype "passive"))
      (node (ref "R17") (pin "1") (pinfunction "1_1") (pintype "passive"))
      (node (ref "R41") (pin "2") (pinfunction "2_2") (pintype "passive"))
      (node (ref "R58") (pin "1") (pinfunction "1_1") (pintype "passive"))
      (node (ref "R59") (pin "1") (pinfunction "1_1") (pintype "passive"))
      (node (ref "SV5") (pin "6") (pinfunction "6_6") (pintype "passive"))
      (node (ref "T14") (pin "P$6") (pinfunction "D_P$6") (pintype "passive"))
    )
    (net (code "16") (name "/CELL6") (class "Default")
      (node (ref "C44") (pin "1") (pinfunction "1_1") (pintype "passive"))
      (node (ref "R1B") (pin "1") (pinfunction "1_1") (pintype "passive"))
      (node (ref "R32") (pin "1") (pinfunction "1_1") (pintype "passive"))
      (node (ref "R42") (pin "2") (pinfunction "2_2") (pintype "passive"))
      (node (ref "SV5") (pin "7") (pinfunction "7_7") (pintype "passive"))
    )
    (net (code "17") (name "/CELLGND") (class "Default")
      (node (ref "C50") (pin "1") (pinfunction "1_1") (pintype "passive"))
      (node (ref "R14") (pin "2") (pinfunction "2_2") (pintype "passive"))
      (node (ref "R25") (pin "1") (pinfunction "1_1") (pintype "passive"))
      (node (ref "SV5") (pin "1") (pinfunction "1_1") (pintype "passive"))
      (node (ref "T8") (pin "P$6") (pinfunction "D_P$6") (pintype "passive"))
    )
    (net (code "18") (name "/I_ACT_HI") (class "Default")
      (node (ref "C9") (pin "2") (pinfunction "2_2") (pintype "passive"))
      (node (ref "IC3") (pin "3") (pinfunction "PA7_3") (pintype "bidirectional"))
      (node (ref "R92") (pin "1") (pinfunction "1_1") (pintype "passive"))
    )
    (net (code "19") (name "/I_ACT_LOW") (class "Default")
      (node (ref "C29") (pin "2") (pinfunction "2_2") (pintype "passive"))
      (node (ref "IC3") (pin "2") (pinfunction "PA6_2") (pintype "bidirectional"))
      (node (ref "R91") (pin "1") (pinfunction "1_1") (pintype "passive"))
    )
    (net (code "20") (name "/LED1") (class "Default")
      (node (ref "IC3") (pin "23") (pinfunction "PD3_23") (pintype "bidirectional"))
      (node (ref "R12") (pin "1") (pinfunction "1_1") (pintype "passive"))
    )
    (net (code "21") (name "/MISO") (class "Default")
      (node (ref "AUX2") (pin "2") (pinfunction "2_2") (pintype "passive"))
      (node (ref "IC3") (pin "26") (pinfunction "PD6_26") (pintype "bidirectional"))
    )
    (net (code "22") (name "/MOSI") (class "Default")
      (node (ref "AUX2") (pin "1") (pinfunction "1_1") (pintype "passive"))
      (node (ref "IC3") (pin "25") (pinfunction "PD5_25") (pintype "bidirectional"))
    )
    (net (code "23") (name "/PO1") (class "Default")
      (node (ref "IC3") (pin "24") (pinfunction "PD4_24") (pintype "bidirectional"))
      (node (ref "R13") (pin "1") (pinfunction "1_1") (pintype "passive"))
    )
    (net (code "24") (name "/SCK") (class "Default")
      (node (ref "AUX2") (pin "3") (pinfunction "3_3") (pintype "passive"))
      (node (ref "IC3") (pin "27") (pinfunction "PD7_27") (pintype "bidirectional"))
    )
    (net (code "25") (name "/SCL") (class "Default")
      (node (ref "AUX1") (pin "2") (pinfunction "2_2") (pintype "passive"))
      (node (ref "IC3") (pin "29") (pinfunction "PE1_29") (pintype "bidirectional"))
    )
    (net (code "26") (name "/SDA") (class "Default")
      (node (ref "AUX1") (pin "1") (pinfunction "1_1") (pintype "passive"))
      (node (ref "IC3") (pin "28") (pinfunction "PE0_28") (pintype "bidirectional"))
    )
    (net (code "27") (name "/TEMP_MEAS2") (class "Default")
      (node (ref "C36") (pin "2") (pinfunction "2_2") (pintype "passive"))
      (node (ref "IC3") (pin "7") (pinfunction "PB3_7") (pintype "bidirectional"))
      (node (ref "R11") (pin "1") (pinfunction "1_1") (pintype "passive"))
      (node (ref "R15") (pin "2") (pinfunction "2_2") (pintype "passive"))
    )
    (net (code "28") (name "/U_BATT_MEAS") (class "Default")
      (node (ref "C28") (pin "2") (pinfunction "2_2") (pintype "passive"))
      (node (ref "IC3") (pin "4") (pinfunction "PB0_4") (pintype "bidirectional"))
      (node (ref "R31") (pin "1") (pinfunction "1_1") (pintype "passive"))
      (node (ref "R72") (pin "2") (pinfunction "2_2") (pintype "passive"))
    )
    (net (code "29") (name "/U_CELL_M1") (class "Default")
      (node (ref "C1") (pin "2") (pinfunction "2_2") (pintype "passive"))
      (node (ref "IC3") (pin "6") (pinfunction "PB2_6") (pintype "bidirectional"))
      (node (ref "R79") (pin "1") (pinfunction "1_1") (pintype "passive"))
    )
    (net (code "30") (name "/U_CELL_M2") (class "Default")
      (node (ref "C2") (pin "2") (pinfunction "2_2") (pintype "passive"))
      (node (ref "IC3") (pin "41") (pinfunction "PA1_41") (pintype "bidirectional"))
      (node (ref "R80") (pin "1") (pinfunction "1_1") (pintype "passive"))
    )
    (net (code "31") (name "/U_CELL_M3") (class "Default")
      (node (ref "C3") (pin "2") (pinfunction "2_2") (pintype "passive"))
      (node (ref "IC3") (pin "42") (pinfunction "PA2_42") (pintype "bidirectional"))
      (node (ref "R81") (pin "1") (pinfunction "1_1") (pintype "passive"))
    )
    (net (code "32") (name "/U_CELL_M4") (class "Default")
      (node (ref "C4") (pin "2") (pinfunction "2_2") (pintype "passive"))
      (node (ref "IC3") (pin "43") (pinfunction "PA3_43") (pintype "bidirectional"))
      (node (ref "R82") (pin "1") (pinfunction "1_1") (pintype "passive"))
    )
    (net (code "33") (name "/U_CELL_M5") (class "Default")
      (node (ref "C5") (pin "2") (pinfunction "2_2") (pintype "passive"))
      (node (ref "IC3") (pin "44") (pinfunction "PA4_44") (pintype "bidirectional"))
      (node (ref "R83") (pin "1") (pinfunction "1_1") (pintype "passive"))
    )
    (net (code "34") (name "/U_CELL_M6") (class "Default")
      (node (ref "C6") (pin "2") (pinfunction "2_2") (pintype "passive"))
      (node (ref "IC3") (pin "1") (pinfunction "PA5_1") (pintype "bidirectional"))
      (node (ref "R84") (pin "1") (pinfunction "1_1") (pintype "passive"))
    )
    (net (code "35") (name "/U_SUPP_MEAS") (class "Default")
      (node (ref "C27") (pin "2") (pinfunction "2_2") (pintype "passive"))
      (node (ref "IC3") (pin "5") (pinfunction "PB1_5") (pintype "bidirectional"))
      (node (ref "R29") (pin "1") (pinfunction "1_1") (pintype "passive"))
      (node (ref "R71") (pin "2") (pinfunction "2_2") (pintype "passive"))
    )
    (net (code "37") (name "0V") (class "Default")
      (node (ref "C10") (pin "-") (pinfunction "P-_-") (pintype "bidirectional"))
      (node (ref "C11") (pin "1") (pinfunction "1_1") (pintype "passive"))
      (node (ref "C12") (pin "2") (pinfunction "2_2") (pintype "passive"))
      (node (ref "C15") (pin "1") (pinfunction "1_1") (pintype "passive"))
      (node (ref "C31") (pin "1") (pinfunction "1_1") (pintype "passive"))
      (node (ref "C33") (pin "1") (pinfunction "1_1") (pintype "passive"))
      (node (ref "C34") (pin "-") (pinfunction "P-_-") (pintype "bidirectional"))
      (node (ref "C35") (pin "2") (pinfunction "2_2") (pintype "passive"))
      (node (ref "C37") (pin "2") (pinfunction "2_2") (pintype "passive"))
      (node (ref "C38") (pin "1") (pinfunction "1_1") (pintype "passive"))
      (node (ref "C39") (pin "1") (pinfunction "1_1") (pintype "passive"))
      (node (ref "C40") (pin "1") (pinfunction "1_1") (pintype "passive"))
      (node (ref "C41") (pin "2") (pinfunction "2_2") (pintype "passive"))
      (node (ref "C42") (pin "2") (pinfunction "2_2") (pintype "passive"))
      (node (ref "C43") (pin "2") (pinfunction "2_2") (pintype "passive"))
      (node (ref "C7") (pin "-") (pinfunction "-_-") (pintype "passive"))
      (node (ref "C8") (pin "-") (pinfunction "-_-") (pintype "passive"))
      (node (ref "LED1") (pin "K") (pinfunction "C_K") (pintype "passive"))
      (node (ref "R1") (pin "1") (pinfunction "1_1") (pintype "passive"))
      (node (ref "R100") (pin "2") (pinfunction "2_2") (pintype "passive"))
      (node (ref "R101") (pin "2") (pinfunction "2_2") (pintype "passive"))
      (node (ref "R16") (pin "2") (pinfunction "2_2") (pintype "passive"))
      (node (ref "R20") (pin "1") (pinfunction "1_1") (pintype "passive"))
      (node (ref "R24") (pin "2") (pinfunction "2_2") (pintype "passive"))
      (node (ref "R7") (pin "1") (pinfunction "1_1") (pintype "passive"))
      (node (ref "R73") (pin "2") (pinfunction "2_2") (pintype "passive"))
      (node (ref "R86") (pin "2") (pinfunction "2_2") (pintype "passive"))
      (node (ref "R90") (pin "2") (pinfunction "2_2") (pintype "passive"))
      (node (ref "T10") (pin "P$2") (pinfunction "S_P$2") (pintype "passive"))
      (node (ref "T10") (pin "P$5") (pinfunction "S_P$5") (pintype "passive"))
      (node (ref "T11") (pin "3") (pinfunction "S_3") (pintype "passive"))
      (node (ref "T2") (pin "3") (pinfunction "S_3") (pintype "passive"))
      (node (ref "T4") (pin "3") (pinfunction "S_3") (pintype "passive"))
      (node (ref "U$3") (pin "9") (pinfunction "VSS_9") (pintype "bidirectional"))
      (node (ref "U$4") (pin "9") (pinfunction "VSS_9") (pintype "bidirectional"))
    )
    (net (code "38") (name "AVCC") (class "Default")
      (node (ref "C23") (pin "2") (pinfunction "2_2") (pintype "passive"))
      (node (ref "IC3") (pin "39") (pinfunction "AVCC_39") (pintype "bidirectional"))
      (node (ref "L7") (pin "1") (pinfunction "1_1") (pintype "passive"))
      (node (ref "R97") (pin "1") (pinfunction "1_1") (pintype "passive"))
    )
    (net (code "39") (name "BATT-") (class "Default")
      (node (ref "C37") (pin "1") (pinfunction "1_1") (pintype "passive"))
      (node (ref "D5") (pin "A") (pinfunction "A_A") (pintype "passive"))
      (node (ref "R14") (pin "1") (pinfunction "1_1") (pintype "passive"))
      (node (ref "T5") (pin "4") (pinfunction "D_4") (pintype "passive"))
      (node (ref "U$6") (pin "P$1") (pinfunction "P$1_P$1") (pintype "bidirectional"))
    )
    (net (code "40") (name "BATT-B") (class "Default")
      (node (ref "R20") (pin "2") (pinfunction "2_2") (pintype "passive"))
      (node (ref "R95") (pin "2") (pinfunction "2_2") (pintype "passive"))
      (node (ref "T5") (pin "3") (pinfunction "S_3") (pintype "passive"))
    )
    (net (code "41") (name "BUS_GND") (class "Default")
      (node (ref "SV4") (pin "2") (pinfunction "2_2") (pintype "passive"))
    )
    (net (code "42") (name "BUS_TX") (class "Default")
      (node (ref "OK1") (pin "5") (pinfunction "EMIT_5") (pintype "passive"))
      (node (ref "SV4") (pin "4") (pinfunction "4_4") (pintype "passive"))
    )
    (net (code "43") (name "GND") (class "Default")
      (node (ref "AUX1") (pin "4") (pinfunction "4_4") (pintype "passive"))
      (node (ref "AUX2") (pin "4") (pinfunction "4_4") (pintype "passive"))
      (node (ref "C1") (pin "1") (pinfunction "1_1") (pintype "passive"))
      (node (ref "C13") (pin "1") (pinfunction "1_1") (pintype "passive"))
      (node (ref "C14") (pin "1") (pinfunction "1_1") (pintype "passive"))
      (node (ref "C16") (pin "1") (pinfunction "1_1") (pintype "passive"))
      (node (ref "C17") (pin "1") (pinfunction "1_1") (pintype "passive"))
      (node (ref "C18") (pin "1") (pinfunction "1_1") (pintype "passive"))
      (node (ref "C19") (pin "-") (pinfunction "-_-") (pintype "passive"))
      (node (ref "C2") (pin "1") (pinfunction "1_1") (pintype "passive"))
      (node (ref "C20") (pin "-") (pinfunction "-_-") (pintype "passive"))
      (node (ref "C21") (pin "1") (pinfunction "1_1") (pintype "passive"))
      (node (ref "C22") (pin "1") (pinfunction "1_1") (pintype "passive"))
      (node (ref "C23") (pin "1") (pinfunction "1_1") (pintype "passive"))
      (node (ref "C24") (pin "1") (pinfunction "1_1") (pintype "passive"))
      (node (ref "C25") (pin "1") (pinfunction "1_1") (pintype "passive"))
      (node (ref "C26") (pin "1") (pinfunction "1_1") (pintype "passive"))
      (node (ref "C27") (pin "1") (pinfunction "1_1") (pintype "passive"))
      (node (ref "C28") (pin "1") (pinfunction "1_1") (pintype "passive"))
      (node (ref "C29") (pin "1") (pinfunction "1_1") (pintype "passive"))
      (node (ref "C3") (pin "1") (pinfunction "1_1") (pintype "passive"))
      (node (ref "C36") (pin "1") (pinfunction "1_1") (pintype "passive"))
      (node (ref "C4") (pin "1") (pinfunction "1_1") (pintype "passive"))
      (node (ref "C44") (pin "2") (pinfunction "2_2") (pintype "passive"))
      (node (ref "C45") (pin "2") (pinfunction "2_2") (pintype "passive"))
      (node (ref "C46") (pin "2") (pinfunction "2_2") (pintype "passive"))
      (node (ref "C47") (pin "2") (pinfunction "2_2") (pintype "passive"))
      (node (ref "C48") (pin "2") (pinfunction "2_2") (pintype "passive"))
      (node (ref "C49") (pin "2") (pinfunction "2_2") (pintype "passive"))
      (node (ref "C5") (pin "1") (pinfunction "1_1") (pintype "passive"))
      (node (ref "C50") (pin "2") (pinfunction "2_2") (pintype "passive"))
      (node (ref "C6") (pin "1") (pinfunction "1_1") (pintype "passive"))
      (node (ref "C9") (pin "1") (pinfunction "1_1") (pintype "passive"))
      (node (ref "D7") (pin "C") (pinfunction "C_C") (pintype "passive"))
      (node (ref "IC1") (pin "11") (pinfunction "V-_11") (pintype "power_in"))
      (node (ref "IC2") (pin "11") (pinfunction "V-_11") (pintype "power_in"))
      (node (ref "IC3") (pin "18") (pinfunction "GND2_18") (pintype "bidirectional"))
      (node (ref "IC3") (pin "30") (pinfunction "GND3_30") (pintype "bidirectional"))
      (node (ref "IC3") (pin "38") (pinfunction "AGND_38") (pintype "bidirectional"))
      (node (ref "IC3") (pin "40") (pinfunction "PA0_40") (pintype "bidirectional"))
      (node (ref "IC3") (pin "8") (pinfunction "GND1_8") (pintype "bidirectional"))
      (node (ref "OK1") (pin "4") (pinfunction "C_4") (pintype "passive"))
      (node (ref "Q10") (pin "E") (pinfunction "E_E") (pintype "passive"))
      (node (ref "Q11") (pin "E") (pinfunction "E_E") (pintype "passive"))
      (node (ref "Q2") (pin "E") (pinfunction "E_E") (pintype "passive"))
      (node (ref "Q7") (pin "E") (pinfunction "E_E") (pintype "passive"))
      (node (ref "Q8") (pin "E") (pinfunction "E_E") (pintype "passive"))
      (node (ref "Q9") (pin "E") (pinfunction "E_E") (pintype "passive"))
      (node (ref "R101") (pin "1") (pinfunction "1_1") (pintype "passive"))
      (node (ref "R29") (pin "2") (pinfunction "2_2") (pintype "passive"))
      (node (ref "R2B") (pin "1") (pinfunction "1_1") (pintype "passive"))
      (node (ref "R31") (pin "2") (pinfunction "2_2") (pintype "passive"))
      (node (ref "R34") (pin "1") (pinfunction "1_1") (pintype "passive"))
      (node (ref "R52") (pin "1") (pinfunction "1_1") (pintype "passive"))
      (node (ref "R61") (pin "1") (pinfunction "1_1") (pintype "passive"))
      (node (ref "R63") (pin "1") (pinfunction "1_1") (pintype "passive"))
      (node (ref "R65") (pin "1") (pinfunction "1_1") (pintype "passive"))
      (node (ref "R68") (pin "2") (pinfunction "2_2") (pintype "passive"))
      (node (ref "R69") (pin "2") (pinfunction "2_2") (pintype "passive"))
      (node (ref "R77") (pin "2") (pinfunction "2_2") (pintype "passive"))
      (node (ref "TP4") (pin "TP") (pinfunction "TP_TP") (pintype "input"))
      (node (ref "U$1") (pin "LEFT") (pinfunction "GND_LEFT") (pintype "bidirectional"))
    )
    (net (code "44") (name "Net-(D6-PadC)") (class "Default")
      (node (ref "D6") (pin "C") (pinfunction "C_C") (pintype "passive"))
      (node (ref "SV4") (pin "5") (pinfunction "5_5") (pintype "passive"))
    )
    (net (code "45") (name "Net-(D7-PadA)") (class "Default")
      (node (ref "D7") (pin "A") (pinfunction "A_A") (pintype "passive"))
      (node (ref "SV4") (pin "6") (pinfunction "6_6") (pintype "passive"))
    )
    (net (code "46") (name "Net-(F1-Pad2)") (class "Default")
      (node (ref "F1") (pin "2") (pinfunction "2_2") (pintype "passive"))
      (node (ref "SUPP+") (pin "P$1") (pinfunction "P$1_P$1") (pintype "bidirectional"))
    )
    (net (code "47") (name "Net-(F2-Pad2)") (class "Default")
      (node (ref "F2") (pin "2") (pinfunction "2_2") (pintype "passive"))
      (node (ref "U$5") (pin "P$1") (pinfunction "P$1_P$1") (pintype "bidirectional"))
    )
    (net (code "48") (name "Net-(IC1A-+IN)") (class "Default")
      (node (ref "C13") (pin "2") (pinfunction "2_2") (pintype "passive"))
      (node (ref "IC1") (pin "3") (pinfunction "+IN_3") (pintype "input"))
      (node (ref "R95") (pin "1") (pinfunction "1_1") (pintype "passive"))
      (node (ref "R97") (pin "2") (pinfunction "2_2") (pintype "passive"))
    )
    (net (code "49") (name "Net-(IC1A--IN)") (class "Default")
      (node (ref "IC1") (pin "2") (pinfunction "-IN_2") (pintype "input"))
      (node (ref "R69") (pin "1") (pinfunction "1_1") (pintype "passive"))
      (node (ref "R70") (pin "2") (pinfunction "2_2") (pintype "passive"))
    )
    (net (code "50") (name "Net-(IC1A-OUT)") (class "Default")
      (node (ref "IC1") (pin "1") (pinfunction "OUT_1") (pintype "output"))
      (node (ref "R70") (pin "1") (pinfunction "1_1") (pintype "passive"))
      (node (ref "R92") (pin "2") (pinfunction "2_2") (pintype "passive"))
    )
    (net (code "51") (name "Net-(IC1B--IN)") (class "Default")
      (node (ref "IC1") (pin "6") (pinfunction "-IN_6") (pintype "input"))
      (node (ref "R67") (pin "2") (pinfunction "2_2") (pintype "passive"))
      (node (ref "R68") (pin "1") (pinfunction "1_1") (pintype "passive"))
    )
    (net (code "52") (name "Net-(IC1B-OUT)") (class "Default")
      (node (ref "IC1") (pin "7") (pinfunction "OUT_7") (pintype "output"))
      (node (ref "R67") (pin "1") (pinfunction "1_1") (pintype "passive"))
      (node (ref "R91") (pin "2") (pinfunction "2_2") (pintype "passive"))
    )
    (net (code "53") (name "Net-(IC1C-+IN)") (class "Default")
      (node (ref "IC1") (pin "10") (pinfunction "+IN_10") (pintype "input"))
      (node (ref "R1B") (pin "2") (pinfunction "2_2") (pintype "passive"))
      (node (ref "R2B") (pin "2") (pinfunction "2_2") (pintype "passive"))
    )
    (net (code "54") (name "Net-(IC1C--IN)") (class "Default")
      (node (ref "IC1") (pin "9") (pinfunction "-IN_9") (pintype "input"))
      (node (ref "R59") (pin "2") (pinfunction "2_2") (pintype "passive"))
      (node (ref "R66") (pin "2") (pinfunction "2_2") (pintype "passive"))
    )
    (net (code "55") (name "Net-(IC1C-OUT)") (class "Default")
      (node (ref "IC1") (pin "8") (pinfunction "OUT_8") (pintype "output"))
      (node (ref "R66") (pin "1") (pinfunction "1_1") (pintype "passive"))
      (node (ref "R84") (pin "2") (pinfunction "2_2") (pintype "passive"))
    )
    (net (code "56") (name "Net-(IC1D-+IN)") (class "Default")
      (node (ref "IC1") (pin "12") (pinfunction "+IN_12") (pintype "input"))
      (node (ref "R58") (pin "2") (pinfunction "2_2") (pintype "passive"))
      (node (ref "R65") (pin "2") (pinfunction "2_2") (pintype "passive"))
    )
    (net (code "57") (name "Net-(IC1D--IN)") (class "Default")
      (node (ref "IC1") (pin "13") (pinfunction "-IN_13") (pintype "input"))
      (node (ref "R57") (pin "2") (pinfunction "2_2") (pintype "passive"))
      (node (ref "R64") (pin "2") (pinfunction "2_2") (pintype "passive"))
    )
    (net (code "58") (name "Net-(IC1D-OUT)") (class "Default")
      (node (ref "IC1") (pin "14") (pinfunction "OUT_14") (pintype "output"))
      (node (ref "R64") (pin "1") (pinfunction "1_1") (pintype "passive"))
      (node (ref "R83") (pin "2") (pinfunction "2_2") (pintype "passive"))
    )
    (net (code "59") (name "Net-(IC1E-V+)") (class "Default")
      (node (ref "C14") (pin "2") (pinfunction "2_2") (pintype "passive"))
      (node (ref "C16") (pin "2") (pinfunction "2_2") (pintype "passive"))
      (node (ref "C40") (pin "2") (pinfunction "2_2") (pintype "passive"))
      (node (ref "D1") (pin "C") (pinfunction "C_C") (pintype "passive"))
      (node (ref "D4") (pin "C") (pinfunction "C_C") (pintype "passive"))
      (node (ref "IC1") (pin "4") (pinfunction "V+_4") (pintype "power_in"))
      (node (ref "IC2") (pin "4") (pinfunction "V+_4") (pintype "power_in"))
    )
    (net (code "60") (name "Net-(IC2A-+IN)") (class "Default")
      (node (ref "IC2") (pin "3") (pinfunction "+IN_3") (pintype "input"))
      (node (ref "R56") (pin "2") (pinfunction "2_2") (pintype "passive"))
      (node (ref "R63") (pin "2") (pinfunction "2_2") (pintype "passive"))
    )
    (net (code "61") (name "Net-(IC2A--IN)") (class "Default")
      (node (ref "IC2") (pin "2") (pinfunction "-IN_2") (pintype "input"))
      (node (ref "R55") (pin "2") (pinfunction "2_2") (pintype "passive"))
      (node (ref "R62") (pin "2") (pinfunction "2_2") (pintype "passive"))
    )
    (net (code "62") (name "Net-(IC2A-OUT)") (class "Default")
      (node (ref "IC2") (pin "1") (pinfunction "OUT_1") (pintype "output"))
      (node (ref "R62") (pin "1") (pinfunction "1_1") (pintype "passive"))
      (node (ref "R82") (pin "2") (pinfunction "2_2") (pintype "passive"))
    )
    (net (code "63") (name "Net-(IC2B-+IN)") (class "Default")
      (node (ref "IC2") (pin "5") (pinfunction "+IN_5") (pintype "input"))
      (node (ref "R54") (pin "2") (pinfunction "2_2") (pintype "passive"))
      (node (ref "R61") (pin "2") (pinfunction "2_2") (pintype "passive"))
    )
    (net (code "64") (name "Net-(IC2B--IN)") (class "Default")
      (node (ref "IC2") (pin "6") (pinfunction "-IN_6") (pintype "input"))
      (node (ref "R53") (pin "2") (pinfunction "2_2") (pintype "passive"))
      (node (ref "R60") (pin "2") (pinfunction "2_2") (pintype "passive"))
    )
    (net (code "65") (name "Net-(IC2B-OUT)") (class "Default")
      (node (ref "IC2") (pin "7") (pinfunction "OUT_7") (pintype "output"))
      (node (ref "R60") (pin "1") (pinfunction "1_1") (pintype "passive"))
      (node (ref "R81") (pin "2") (pinfunction "2_2") (pintype "passive"))
    )
    (net (code "66") (name "Net-(IC2C-+IN)") (class "Default")
      (node (ref "IC2") (pin "10") (pinfunction "+IN_10") (pintype "input"))
      (node (ref "R37") (pin "2") (pinfunction "2_2") (pintype "passive"))
      (node (ref "R52") (pin "2") (pinfunction "2_2") (pintype "passive"))
    )
    (net (code "67") (name "Net-(IC2C--IN)") (class "Default")
      (node (ref "IC2") (pin "9") (pinfunction "-IN_9") (pintype "input"))
      (node (ref "R35") (pin "2") (pinfunction "2_2") (pintype "passive"))
      (node (ref "R36") (pin "2") (pinfunction "2_2") (pintype "passive"))
    )
    (net (code "68") (name "Net-(IC2C-OUT)") (class "Default")
      (node (ref "IC2") (pin "8") (pinfunction "OUT_8") (pintype "output"))
      (node (ref "R35") (pin "1") (pinfunction "1_1") (pintype "passive"))
      (node (ref "R80") (pin "2") (pinfunction "2_2") (pintype "passive"))
    )
    (net (code "69") (name "Net-(IC2D-+IN)") (class "Default")
      (node (ref "IC2") (pin "12") (pinfunction "+IN_12") (pintype "input"))
      (node (ref "R33") (pin "2") (pinfunction "2_2") (pintype "passive"))
      (node (ref "R34") (pin "2") (pinfunction "2_2") (pintype "passive"))
    )
    (net (code "70") (name "Net-(IC2D--IN)") (class "Default")
      (node (ref "IC2") (pin "13") (pinfunction "-IN_13") (pintype "input"))
      (node (ref "R25") (pin "2") (pinfunction "2_2") (pintype "passive"))
      (node (ref "R27") (pin "2") (pinfunction "2_2") (pintype "passive"))
    )
    (net (code "71") (name "Net-(IC2D-OUT)") (class "Default")
      (node (ref "IC2") (pin "14") (pinfunction "OUT_14") (pintype "output"))
      (node (ref "R27") (pin "1") (pinfunction "1_1") (pintype "passive"))
      (node (ref "R79") (pin "2") (pinfunction "2_2") (pintype "passive"))
    )
    (net (code "72") (name "Net-(IC3-PR0)") (class "Default")
      (node (ref "C21") (pin "2") (pinfunction "2_2") (pintype "passive"))
      (node (ref "IC3") (pin "36") (pinfunction "PR0_36") (pintype "bidirectional"))
      (node (ref "QU") (pin "2") (pinfunction "2_2") (pintype "passive"))
    )
    (net (code "73") (name "Net-(IC3-PR1)") (class "Default")
      (node (ref "C22") (pin "2") (pinfunction "2_2") (pintype "passive"))
      (node (ref "IC3") (pin "37") (pinfunction "PR1_37") (pintype "bidirectional"))
      (node (ref "QU") (pin "1") (pinfunction "1_1") (pintype "passive"))
    )
    (net (code "74") (name "Net-(IC4-ADJ)") (class "Default")
      (node (ref "IC4") (pin "1") (pinfunction "ADJ_1") (pintype "input"))
      (node (ref "R23") (pin "2") (pinfunction "2_2") (pintype "passive"))
      (node (ref "R24") (pin "1") (pinfunction "1_1") (pintype "passive"))
    )
    (net (code "75") (name "Net-(LED1-PadA)") (class "Default")
      (node (ref "LED1") (pin "A") (pinfunction "A_A") (pintype "passive"))
      (node (ref "R12") (pin "2") (pinfunction "2_2") (pintype "passive"))
    )
    (net (code "76") (name "Net-(OK1A-A)") (class "Default")
      (node (ref "OK1") (pin "1") (pinfunction "A_1") (pintype "passive"))
      (node (ref "R74") (pin "2") (pinfunction "2_2") (pintype "passive"))
    )
    (net (code "77") (name "Net-(OK1A-C)") (class "Default")
      (node (ref "OK1") (pin "2") (pinfunction "C_2") (pintype "passive"))
      (node (ref "SV4") (pin "3") (pinfunction "3_3") (pintype "passive"))
    )
    (net (code "78") (name "Net-(OK1B-A)") (class "Default")
      (node (ref "OK1") (pin "3") (pinfunction "A_3") (pintype "passive"))
      (node (ref "R76") (pin "1") (pinfunction "1_1") (pintype "passive"))
    )
    (net (code "79") (name "Net-(OK1B-COL)") (class "Default")
      (node (ref "OK1") (pin "6") (pinfunction "COL_6") (pintype "passive"))
      (node (ref "R74") (pin "1") (pinfunction "1_1") (pintype "passive"))
      (node (ref "SV4") (pin "1") (pinfunction "1_1") (pintype "passive"))
    )
    (net (code "80") (name "Net-(Q2-PadB)") (class "Default")
      (node (ref "Q2") (pin "B") (pinfunction "B_B") (pintype "passive"))
      (node (ref "R48") (pin "2") (pinfunction "2_2") (pintype "passive"))
    )
    (net (code "81") (name "Net-(Q7-PadB)") (class "Default")
      (node (ref "Q7") (pin "B") (pinfunction "B_B") (pintype "passive"))
      (node (ref "R43") (pin "2") (pinfunction "2_2") (pintype "passive"))
    )
    (net (code "82") (name "Net-(Q8-PadB)") (class "Default")
      (node (ref "Q8") (pin "B") (pinfunction "B_B") (pintype "passive"))
      (node (ref "R44") (pin "2") (pinfunction "2_2") (pintype "passive"))
    )
    (net (code "83") (name "Net-(Q9-PadB)") (class "Default")
      (node (ref "Q9") (pin "B") (pinfunction "B_B") (pintype "passive"))
      (node (ref "R45") (pin "2") (pinfunction "2_2") (pintype "passive"))
    )
    (net (code "84") (name "Net-(Q9-PadC)") (class "Default")
      (node (ref "Q9") (pin "C") (pinfunction "C_C") (pintype "passive"))
      (node (ref "R6") (pin "1") (pinfunction "1_1") (pintype "passive"))
    )
    (net (code "85") (name "Net-(Q10-PadB)") (class "Default")
      (node (ref "Q10") (pin "B") (pinfunction "B_B") (pintype "passive"))
      (node (ref "R46") (pin "2") (pinfunction "2_2") (pintype "passive"))
    )
    (net (code "86") (name "Net-(Q10-PadC)") (class "Default")
      (node (ref "Q10") (pin "C") (pinfunction "C_C") (pintype "passive"))
      (node (ref "R50") (pin "1") (pinfunction "1_1") (pintype "passive"))
    )
    (net (code "87") (name "Net-(Q11-PadB)") (class "Default")
      (node (ref "Q11") (pin "B") (pinfunction "B_B") (pintype "passive"))
      (node (ref "R47") (pin "2") (pinfunction "2_2") (pintype "passive"))
    )
    (net (code "88") (name "Net-(Q11-PadC)") (class "Default")
      (node (ref "Q11") (pin "C") (pinfunction "C_C") (pintype "passive"))
      (node (ref "R49") (pin "1") (pinfunction "1_1") (pintype "passive"))
    )
    (net (code "89") (name "Net-(R1-Pad2)") (class "Default")
      (node (ref "R1") (pin "2") (pinfunction "2_2") (pintype "passive"))
      (node (ref "R15") (pin "1") (pinfunction "1_1") (pintype "passive"))
      (node (ref "R7") (pin "2") (pinfunction "2_2") (pintype "passive"))
    )
    (net (code "90") (name "Net-(T1-G)") (class "Default")
      (node (ref "R4") (pin "1") (pinfunction "1_1") (pintype "passive"))
      (node (ref "T1") (pin "1") (pinfunction "G_1") (pintype "passive"))
    )
    (net (code "91") (name "Net-(T1-S)") (class "Default")
      (node (ref "C30") (pin "1") (pinfunction "1_1") (pintype "passive"))
      (node (ref "COIL1") (pin "P$1") (pinfunction "P$1_P$1") (pintype "bidirectional"))
      (node (ref "L1") (pin "1") (pinfunction "1_1") (pintype "passive"))
      (node (ref "T1") (pin "3") (pinfunction "S_3") (pintype "passive"))
      (node (ref "T2") (pin "4") (pinfunction "D_4") (pintype "passive"))
      (node (ref "U$3") (pin "4") (pinfunction "HS_4") (pintype "bidirectional"))
    )
    (net (code "92") (name "Net-(T2-G)") (class "Default")
      (node (ref "R8") (pin "1") (pinfunction "1_1") (pintype "passive"))
      (node (ref "T2") (pin "1") (pinfunction "G_1") (pintype "passive"))
    )
    (net (code "93") (name "Net-(T3-G)") (class "Default")
      (node (ref "R87") (pin "1") (pinfunction "1_1") (pintype "passive"))
      (node (ref "T3") (pin "1") (pinfunction "G_1") (pintype "passive"))
    )
    (net (code "94") (name "Net-(T3-S)") (class "Default")
      (node (ref "C32") (pin "1") (pinfunction "1_1") (pintype "passive"))
      (node (ref "COIL2") (pin "P$1") (pinfunction "P$1_P$1") (pintype "bidirectional"))
      (node (ref "L1") (pin "2") (pinfunction "2_2") (pintype "passive"))
      (node (ref "T3") (pin "3") (pinfunction "S_3") (pintype "passive"))
      (node (ref "T4") (pin "4") (pinfunction "D_4") (pintype "passive"))
      (node (ref "U$4") (pin "4") (pinfunction "HS_4") (pintype "bidirectional"))
    )
    (net (code "95") (name "Net-(T4-G)") (class "Default")
      (node (ref "R88") (pin "1") (pinfunction "1_1") (pintype "passive"))
      (node (ref "T4") (pin "1") (pinfunction "G_1") (pintype "passive"))
    )
    (net (code "96") (name "Net-(T5-G)") (class "Default")
      (node (ref "D5") (pin "C") (pinfunction "C_C") (pintype "passive"))
      (node (ref "R26") (pin "2") (pinfunction "2_2") (pintype "passive"))
      (node (ref "T5") (pin "1") (pinfunction "G_1") (pintype "passive"))
    )
    (net (code "97") (name "Net-(T8A-G)") (class "Default")
      (node (ref "Q2") (pin "C") (pinfunction "C_C") (pintype "passive"))
      (node (ref "R85") (pin "1") (pinfunction "1_1") (pintype "passive"))
      (node (ref "T8") (pin "P$1") (pinfunction "G_P$1") (pintype "passive"))
    )
    (net (code "98") (name "Net-(T8A-S)") (class "Default")
      (node (ref "R22") (pin "2") (pinfunction "2_2") (pintype "passive"))
      (node (ref "T8") (pin "P$5") (pinfunction "S_P$5") (pintype "passive"))
    )
    (net (code "99") (name "Net-(T8B-G)") (class "Default")
      (node (ref "Q7") (pin "C") (pinfunction "C_C") (pintype "passive"))
      (node (ref "R38") (pin "1") (pinfunction "1_1") (pintype "passive"))
      (node (ref "T8") (pin "P$3") (pinfunction "G_P$3") (pintype "passive"))
    )
    (net (code "100") (name "Net-(T8B-S)") (class "Default")
      (node (ref "R21") (pin "2") (pinfunction "2_2") (pintype "passive"))
      (node (ref "T8") (pin "P$2") (pinfunction "S_P$2") (pintype "passive"))
    )
    (net (code "101") (name "Net-(T9A-G)") (class "Default")
      (node (ref "Q8") (pin "C") (pinfunction "C_C") (pintype "passive"))
      (node (ref "R39") (pin "1") (pinfunction "1_1") (pintype "passive"))
      (node (ref "T9") (pin "P$1") (pinfunction "G_P$1") (pintype "passive"))
    )
    (net (code "102") (name "Net-(T9A-S)") (class "Default")
      (node (ref "R19") (pin "2") (pinfunction "2_2") (pintype "passive"))
      (node (ref "T9") (pin "P$5") (pinfunction "S_P$5") (pintype "passive"))
    )
    (net (code "103") (name "Net-(T9B-G)") (class "Default")
      (node (ref "R40") (pin "1") (pinfunction "1_1") (pintype "passive"))
      (node (ref "R6") (pin "2") (pinfunction "2_2") (pintype "passive"))
      (node (ref "T9") (pin "P$3") (pinfunction "G_P$3") (pintype "passive"))
    )
    (net (code "104") (name "Net-(T9B-S)") (class "Default")
      (node (ref "R18") (pin "2") (pinfunction "2_2") (pintype "passive"))
      (node (ref "T9") (pin "P$2") (pinfunction "S_P$2") (pintype "passive"))
    )
    (net (code "105") (name "Net-(T10A-D)") (class "Default")
      (node (ref "T10") (pin "P$4") (pinfunction "D_P$4") (pintype "passive"))
      (node (ref "T10") (pin "P$6") (pinfunction "D_P$6") (pintype "passive"))
      (node (ref "TP5") (pin "TP") (pinfunction "TP_TP") (pintype "input"))
    )
    (net (code "106") (name "Net-(T10A-G)") (class "Default")
      (node (ref "R13") (pin "2") (pinfunction "2_2") (pintype "passive"))
      (node (ref "T10") (pin "P$1") (pinfunction "G_P$1") (pintype "passive"))
      (node (ref "T10") (pin "P$3") (pinfunction "G_P$3") (pintype "passive"))
    )
    (net (code "107") (name "Net-(T11-D)") (class "Default")
      (node (ref "C43") (pin "1") (pinfunction "1_1") (pintype "passive"))
      (node (ref "SUPP-") (pin "P$1") (pinfunction "P$1_P$1") (pintype "bidirectional"))
      (node (ref "T11") (pin "4") (pinfunction "D_4") (pintype "passive"))
    )
    (net (code "108") (name "Net-(T14A-G)") (class "Default")
      (node (ref "R42") (pin "1") (pinfunction "1_1") (pintype "passive"))
      (node (ref "R49") (pin "2") (pinfunction "2_2") (pintype "passive"))
      (node (ref "T14") (pin "P$1") (pinfunction "G_P$1") (pintype "passive"))
    )
    (net (code "109") (name "Net-(T14A-S)") (class "Default")
      (node (ref "R32") (pin "2") (pinfunction "2_2") (pintype "passive"))
      (node (ref "T14") (pin "P$5") (pinfunction "S_P$5") (pintype "passive"))
    )
    (net (code "110") (name "Net-(T14B-G)") (class "Default")
      (node (ref "R41") (pin "1") (pinfunction "1_1") (pintype "passive"))
      (node (ref "R50") (pin "2") (pinfunction "2_2") (pintype "passive"))
      (node (ref "T14") (pin "P$3") (pinfunction "G_P$3") (pintype "passive"))
    )
    (net (code "111") (name "Net-(T14B-S)") (class "Default")
      (node (ref "R17") (pin "2") (pinfunction "2_2") (pintype "passive"))
      (node (ref "T14") (pin "P$2") (pinfunction "S_P$2") (pintype "passive"))
    )
    (net (code "112") (name "Net-(U$3-EN)") (class "Default")
      (node (ref "R5") (pin "2") (pinfunction "2_2") (pintype "passive"))
      (node (ref "R86") (pin "1") (pinfunction "1_1") (pintype "passive"))
      (node (ref "U$3") (pin "7") (pinfunction "EN_7") (pintype "bidirectional"))
    )
    (net (code "113") (name "Net-(U$3-HB)") (class "Default")
      (node (ref "C30") (pin "2") (pinfunction "2_2") (pintype "passive"))
      (node (ref "D2") (pin "C") (pinfunction "C_C") (pintype "passive"))
      (node (ref "U$3") (pin "2") (pinfunction "HB_2") (pintype "bidirectional"))
    )
    (net (code "114") (name "Net-(U$3-HO)") (class "Default")
      (node (ref "R4") (pin "2") (pinfunction "2_2") (pintype "passive"))
      (node (ref "U$3") (pin "3") (pinfunction "HO_3") (pintype "bidirectional"))
    )
    (net (code "115") (name "Net-(U$3-IN)") (class "Default")
      (node (ref "R3") (pin "2") (pinfunction "2_2") (pintype "passive"))
      (node (ref "U$3") (pin "8") (pinfunction "IN_8") (pintype "bidirectional"))
    )
    (net (code "116") (name "Net-(U$3-LO)") (class "Default")
      (node (ref "R8") (pin "2") (pinfunction "2_2") (pintype "passive"))
      (node (ref "U$3") (pin "10") (pinfunction "LO_10") (pintype "bidirectional"))
    )
    (net (code "117") (name "Net-(U$3-RDT)") (class "Default")
      (node (ref "R73") (pin "1") (pinfunction "1_1") (pintype "passive"))
      (node (ref "U$3") (pin "6") (pinfunction "RDT_6") (pintype "bidirectional"))
    )
    (net (code "118") (name "Net-(U$4-EN)") (class "Default")
      (node (ref "R10") (pin "1") (pinfunction "1_1") (pintype "passive"))
      (node (ref "R90") (pin "1") (pinfunction "1_1") (pintype "passive"))
      (node (ref "U$4") (pin "7") (pinfunction "EN_7") (pintype "bidirectional"))
    )
    (net (code "119") (name "Net-(U$4-HB)") (class "Default")
      (node (ref "C32") (pin "2") (pinfunction "2_2") (pintype "passive"))
      (node (ref "D3") (pin "C") (pinfunction "C_C") (pintype "passive"))
      (node (ref "U$4") (pin "2") (pinfunction "HB_2") (pintype "bidirectional"))
    )
    (net (code "120") (name "Net-(U$4-HO)") (class "Default")
      (node (ref "R87") (pin "2") (pinfunction "2_2") (pintype "passive"))
      (node (ref "U$4") (pin "3") (pinfunction "HO_3") (pintype "bidirectional"))
    )
    (net (code "121") (name "Net-(U$4-IN)") (class "Default")
      (node (ref "R9") (pin "1") (pinfunction "1_1") (pintype "passive"))
      (node (ref "U$4") (pin "8") (pinfunction "IN_8") (pintype "bidirectional"))
    )
    (net (code "122") (name "Net-(U$4-LO)") (class "Default")
      (node (ref "R88") (pin "2") (pinfunction "2_2") (pintype "passive"))
      (node (ref "U$4") (pin "10") (pinfunction "LO_10") (pintype "bidirectional"))
    )
    (net (code "123") (name "Net-(U$4-RDT)") (class "Default")
      (node (ref "R100") (pin "1") (pinfunction "1_1") (pintype "passive"))
      (node (ref "U$4") (pin "6") (pinfunction "RDT_6") (pintype "bidirectional"))
    )
    (net (code "124") (name "PDI_CLK") (class "Default")
      (node (ref "IC3") (pin "35") (pinfunction "RESET_35") (pintype "bidirectional"))
      (node (ref "TP2") (pin "TP") (pinfunction "TP_TP") (pintype "input"))
    )
    (net (code "125") (name "PDI_DATA") (class "Default")
      (node (ref "IC3") (pin "34") (pinfunction "PDI_DATA_34") (pintype "bidirectional"))
      (node (ref "TP1") (pin "TP") (pinfunction "TP_TP") (pintype "input"))
    )
    (net (code "126") (name "PWM1") (class "Default")
      (node (ref "IC3") (pin "10") (pinfunction "PC0_10") (pintype "bidirectional"))
      (node (ref "R3") (pin "1") (pinfunction "1_1") (pintype "passive"))
    )
    (net (code "127") (name "PWM1EN") (class "Default")
      (node (ref "IC3") (pin "11") (pinfunction "PC1_11") (pintype "bidirectional"))
      (node (ref "R5") (pin "1") (pinfunction "1_1") (pintype "passive"))
    )
    (net (code "128") (name "PWM2") (class "Default")
      (node (ref "IC3") (pin "20") (pinfunction "PD0_20") (pintype "bidirectional"))
      (node (ref "R9") (pin "2") (pinfunction "2_2") (pintype "passive"))
    )
    (net (code "129") (name "PWM2EN") (class "Default")
      (node (ref "IC3") (pin "21") (pinfunction "PD1_21") (pintype "bidirectional"))
      (node (ref "R10") (pin "2") (pinfunction "2_2") (pintype "passive"))
    )
    (net (code "130") (name "SERIAL_RX") (class "Default")
      (node (ref "IC3") (pin "32") (pinfunction "PE2_32") (pintype "bidirectional"))
      (node (ref "OK1") (pin "7") (pinfunction "EMIT_7") (pintype "passive"))
      (node (ref "R77") (pin "1") (pinfunction "1_1") (pintype "passive"))
    )
    (net (code "131") (name "SERIAL_TX") (class "Default")
      (node (ref "IC3") (pin "33") (pinfunction "PE3_33") (pintype "bidirectional"))
      (node (ref "R76") (pin "2") (pinfunction "2_2") (pintype "passive"))
    )
    (net (code "132") (name "SUPP+") (class "Default")
      (node (ref "C15") (pin "2") (pinfunction "2_2") (pintype "passive"))
      (node (ref "C35") (pin "1") (pinfunction "1_1") (pintype "passive"))
      (node (ref "C38") (pin "2") (pinfunction "2_2") (pintype "passive"))
      (node (ref "C41") (pin "1") (pinfunction "1_1") (pintype "passive"))
      (node (ref "C42") (pin "1") (pinfunction "1_1") (pintype "passive"))
      (node (ref "C7") (pin "+") (pinfunction "+_+") (pintype "passive"))
      (node (ref "C8") (pin "+") (pinfunction "+_+") (pintype "passive"))
      (node (ref "D1") (pin "A") (pinfunction "A_A") (pintype "passive"))
      (node (ref "F1") (pin "1") (pinfunction "1_1") (pintype "passive"))
      (node (ref "IC4") (pin "3") (pinfunction "IN_3") (pintype "input"))
      (node (ref "R71") (pin "1") (pinfunction "1_1") (pintype "passive"))
      (node (ref "T1") (pin "4") (pinfunction "D_4") (pintype "passive"))
      (node (ref "T11") (pin "1") (pinfunction "G_1") (pintype "passive"))
    )
    (net (code "133") (name "unconnected-(IC1B-+IN-Pad5)") (class "Default")
      (node (ref "IC1") (pin "5") (pinfunction "+IN_5") (pintype "input"))
    )
    (net (code "134") (name "unconnected-(IC3-PD2-Pad22)") (class "Default")
      (node (ref "IC3") (pin "22") (pinfunction "PD2_22") (pintype "bidirectional"))
    )
    (net (code "135") (name "unconnected-(SV5-Pad8)") (class "Default")
      (node (ref "SV5") (pin "8") (pinfunction "8_8") (pintype "passive"))
    )
    (net (code "136") (name "unconnected-(SV5-Pad9)") (class "Default")
      (node (ref "SV5") (pin "9") (pinfunction "9_9") (pintype "passive"))
    )
    (net (code "137") (name "unconnected-(SV5-Pad10)") (class "Default")
      (node (ref "SV5") (pin "10") (pinfunction "10_10") (pintype "passive"))
    )
  )
)
